# Sheet1.net
KiCad netlist of a schematic drawn in Altium Designer
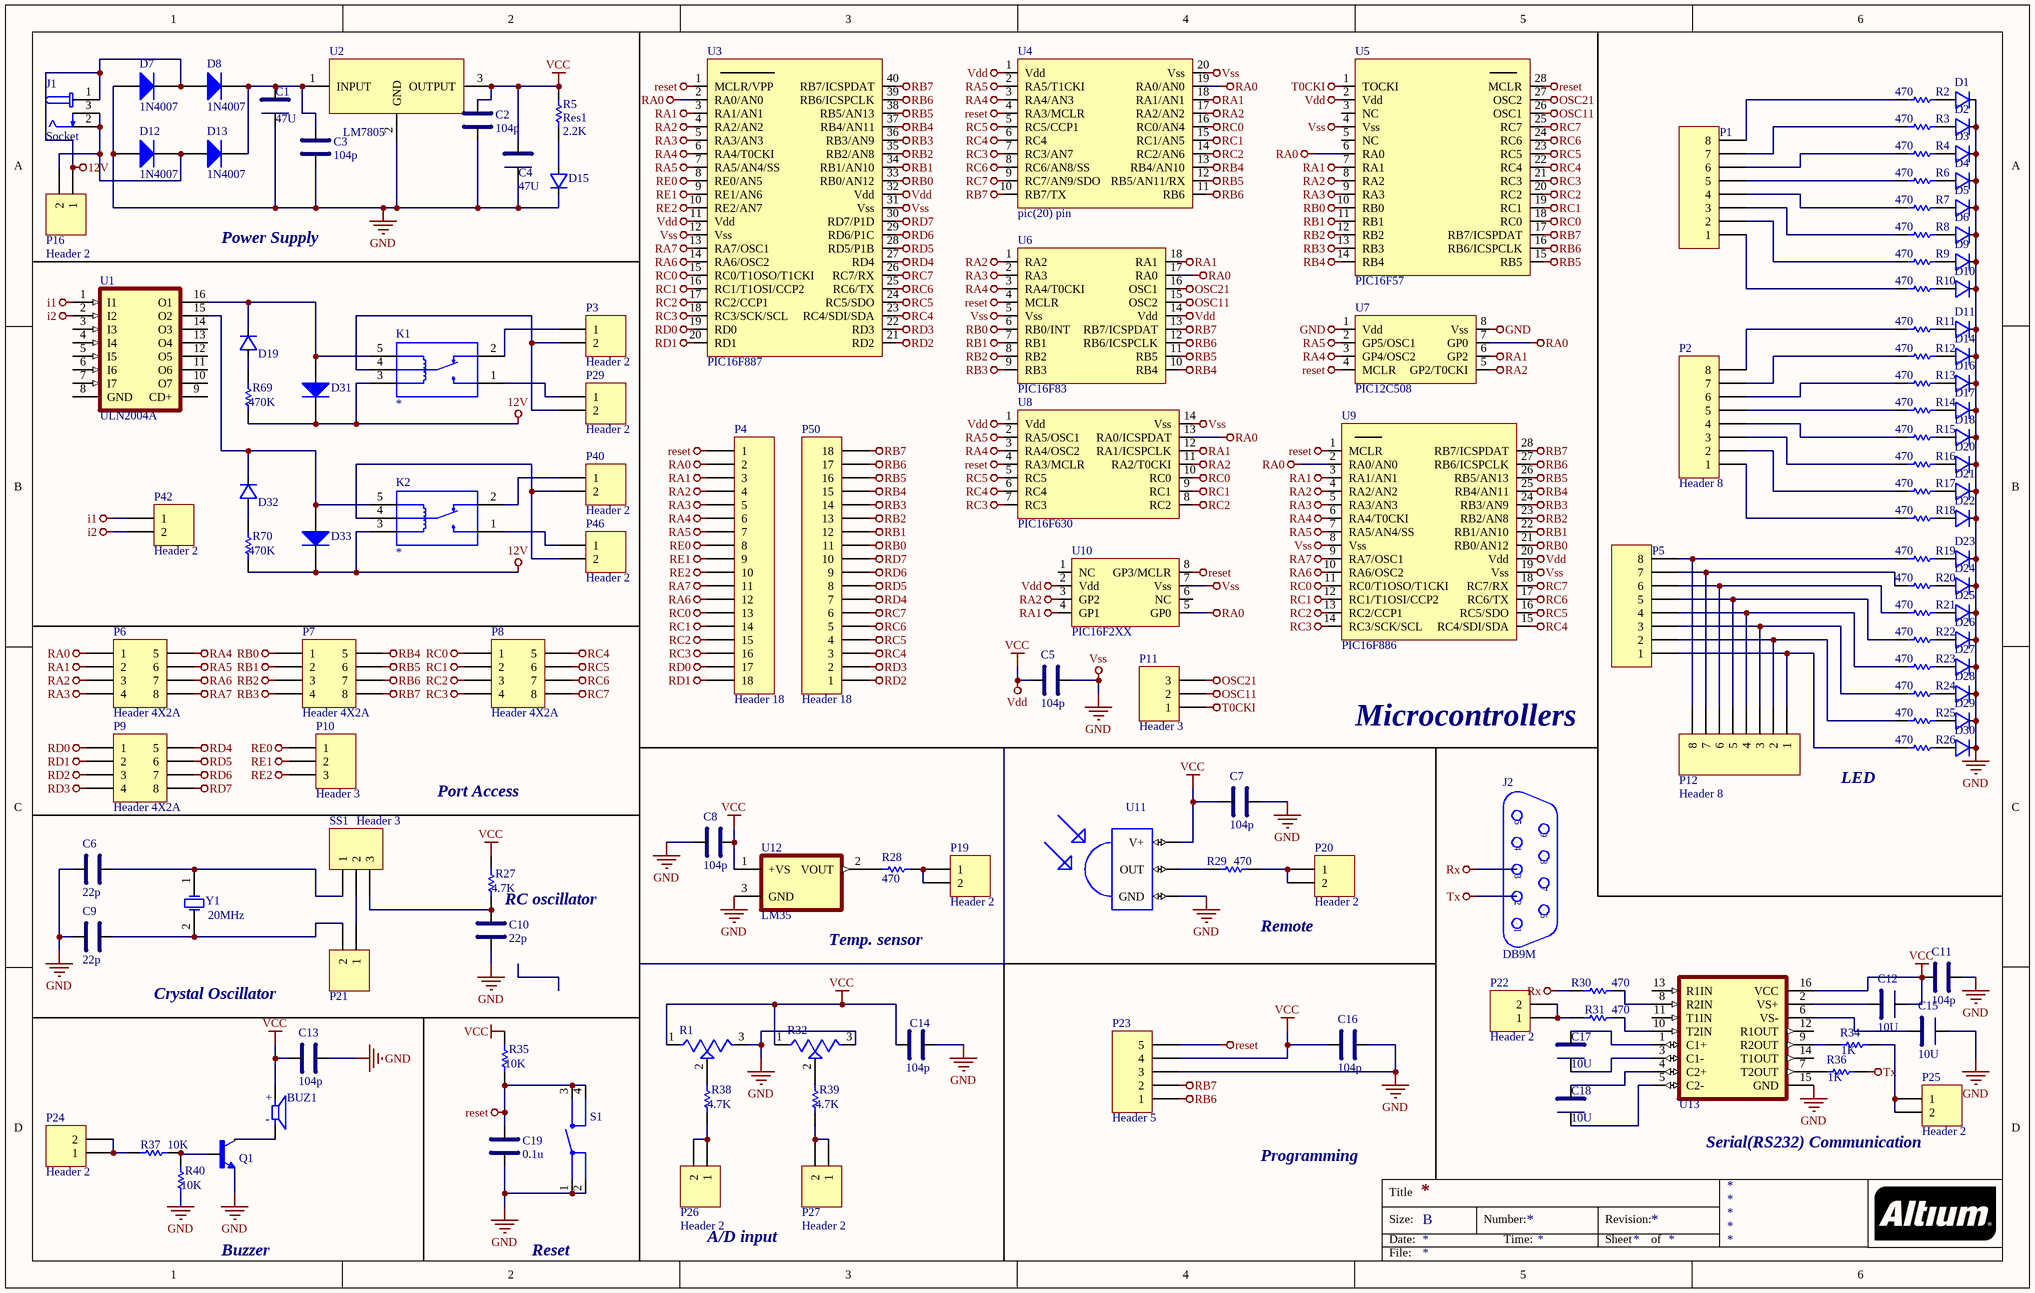
[diagram p0: Sheet1.SchDoc]

(export (version "E")
  (design (tool "Eeschema 10.0.6"))
  (components
    (comp (ref "BUZ1")
      (value "CEM-1203(42)")
      (footprint "SnapEDApcb:CUI_CEM-1203(42)")
      (description "12 mm, 3.5 V, 85 dB, Through Hole, Magnetic Audio Transducer Buzzer")
      (fields (field (name "MF") "CUI Devices") (field (name "MP") "CEM-1203_42_"))
      (libsource (lib "SnapEDAsch") (part "CEM-1203(42)"))
    )
    (comp (ref "C1") (value "47U") (footprint "polarityCAP") (libsource (lib "polarityCAP") (part "CAP")))
    (comp (ref "C2")
      (value "104p")
      (footprint "cap")
      (fields (field (name "Comment") "cap"))
      (libsource (lib "CAP") (part "cap"))
    )
    (comp (ref "C3") (value "104p") (footprint "cap") (libsource (lib "CAP") (part "cap")))
    (comp (ref "C4") (value "47U") (footprint "polarityCAP") (libsource (lib "polarityCAP") (part "CAP")))
    (comp (ref "C5")
      (value "104p")
      (footprint "cap")
      (fields (field (name "Comment") "cap"))
      (libsource (lib "CAP") (part "cap"))
    )
    (comp (ref "C6")
      (value "22p")
      (footprint "cap")
      (fields (field (name "Comment") "cap"))
      (libsource (lib "CAP") (part "cap"))
    )
    (comp (ref "C7")
      (value "104p")
      (footprint "cap")
      (fields (field (name "Comment") "cap"))
      (libsource (lib "CAP") (part "cap"))
    )
    (comp (ref "C8")
      (value "104p")
      (footprint "cap")
      (fields (field (name "Comment") "cap"))
      (libsource (lib "CAP") (part "cap"))
    )
    (comp (ref "C9")
      (value "22p")
      (footprint "cap")
      (fields (field (name "Comment") "cap"))
      (libsource (lib "CAP") (part "cap"))
    )
    (comp (ref "C10")
      (value "22p")
      (footprint "cap")
      (fields (field (name "Comment") "cap"))
      (libsource (lib "CAP") (part "cap"))
    )
    (comp (ref "C11")
      (value "104p")
      (footprint "cap")
      (fields (field (name "Comment") "cap"))
      (libsource (lib "CAP") (part "cap"))
    )
    (comp (ref "C12")
      (value "10U")
      (footprint "polarityCAP")
      (fields (field (name "Comment") "P.CAP"))
      (libsource (lib "polarityCAP") (part "CAP"))
    )
    (comp (ref "C13")
      (value "104p")
      (footprint "cap")
      (fields (field (name "Comment") "cap"))
      (libsource (lib "CAP") (part "cap"))
    )
    (comp (ref "C14")
      (value "104p")
      (footprint "cap")
      (fields (field (name "Comment") "cap"))
      (libsource (lib "CAP") (part "cap"))
    )
    (comp (ref "C15")
      (value "10U")
      (footprint "polarityCAP")
      (fields (field (name "Comment") "P.CAP"))
      (libsource (lib "polarityCAP") (part "CAP"))
    )
    (comp (ref "C16")
      (value "104p")
      (footprint "cap")
      (fields (field (name "Comment") "cap"))
      (libsource (lib "CAP") (part "cap"))
    )
    (comp (ref "C17")
      (value "10U")
      (footprint "polarityCAP")
      (fields (field (name "Comment") "P.CAP"))
      (libsource (lib "polarityCAP") (part "CAP"))
    )
    (comp (ref "C18")
      (value "10U")
      (footprint "polarityCAP")
      (fields (field (name "Comment") "P.CAP"))
      (libsource (lib "polarityCAP") (part "CAP"))
    )
    (comp (ref "C19")
      (value "0.1u")
      (footprint "cap")
      (fields (field (name "Comment") "cap"))
      (libsource (lib "CAP") (part "cap"))
    )
    (comp (ref "D1") (value "LED") (footprint "led:PCBComponent_1") (libsource (lib "led") (part "LED")))
    (comp (ref "D2") (value "LED") (footprint "led:PCBComponent_1") (libsource (lib "led") (part "LED")))
    (comp (ref "D3") (value "LED") (footprint "led:PCBComponent_1") (libsource (lib "led") (part "LED")))
    (comp (ref "D4") (value "LED") (footprint "led:PCBComponent_1") (libsource (lib "led") (part "LED")))
    (comp (ref "D5") (value "LED") (footprint "led:PCBComponent_1") (libsource (lib "led") (part "LED")))
    (comp (ref "D6") (value "LED") (footprint "led:PCBComponent_1") (libsource (lib "led") (part "LED")))
    (comp (ref "D7")
      (value "1N4007")
      (footprint "DO-41")
      (description "1 Amp General Purpose Rectifier")
      (fields (field (name "PUBLISHER") "Altium Limited"))
      (libsource (lib "Miscellaneous Devices") (part "Diode 1N4007"))
    )
    (comp (ref "D8")
      (value "1N4007")
      (footprint "DO-41")
      (description "1 Amp General Purpose Rectifier")
      (fields (field (name "PUBLISHER") "Altium Limited"))
      (libsource (lib "Miscellaneous Devices") (part "Diode 1N4007"))
    )
    (comp (ref "D9") (value "LED") (footprint "led:PCBComponent_1") (libsource (lib "led") (part "LED")))
    (comp (ref "D10") (value "LED") (footprint "led:PCBComponent_1") (libsource (lib "led") (part "LED")))
    (comp (ref "D11") (value "LED") (footprint "led:PCBComponent_1") (libsource (lib "led") (part "LED")))
    (comp (ref "D12")
      (value "1N4007")
      (footprint "DO-41")
      (description "1 Amp General Purpose Rectifier")
      (fields (field (name "PUBLISHER") "Altium Limited"))
      (libsource (lib "Miscellaneous Devices") (part "Diode 1N4007"))
    )
    (comp (ref "D13")
      (value "1N4007")
      (footprint "DO-41")
      (description "1 Amp General Purpose Rectifier")
      (fields (field (name "PUBLISHER") "Altium Limited"))
      (libsource (lib "Miscellaneous Devices") (part "Diode 1N4007"))
    )
    (comp (ref "D14") (value "LED") (footprint "led:PCBComponent_1") (libsource (lib "led") (part "LED")))
    (comp (ref "D15") (value "LED") (footprint "led:PCBComponent_1") (libsource (lib "led") (part "LED")))
    (comp (ref "D16") (value "LED") (footprint "led:PCBComponent_1") (libsource (lib "led") (part "LED")))
    (comp (ref "D17") (value "LED") (footprint "led:PCBComponent_1") (libsource (lib "led") (part "LED")))
    (comp (ref "D18") (value "LED") (footprint "led:PCBComponent_1") (libsource (lib "led") (part "LED")))
    (comp (ref "D19") (value "LED") (footprint "led:PCBComponent_1") (libsource (lib "led") (part "LED")))
    (comp (ref "D20") (value "LED") (footprint "led:PCBComponent_1") (libsource (lib "led") (part "LED")))
    (comp (ref "D21") (value "LED") (footprint "led:PCBComponent_1") (libsource (lib "led") (part "LED")))
    (comp (ref "D22") (value "LED") (footprint "led:PCBComponent_1") (libsource (lib "led") (part "LED")))
    (comp (ref "D23") (value "LED") (footprint "led:PCBComponent_1") (libsource (lib "led") (part "LED")))
    (comp (ref "D24") (value "LED") (footprint "led:PCBComponent_1") (libsource (lib "led") (part "LED")))
    (comp (ref "D25") (value "LED") (footprint "led:PCBComponent_1") (libsource (lib "led") (part "LED")))
    (comp (ref "D26") (value "LED") (footprint "led:PCBComponent_1") (libsource (lib "led") (part "LED")))
    (comp (ref "D27") (value "LED") (footprint "led:PCBComponent_1") (libsource (lib "led") (part "LED")))
    (comp (ref "D28") (value "LED") (footprint "led:PCBComponent_1") (libsource (lib "led") (part "LED")))
    (comp (ref "D29") (value "LED") (footprint "led:PCBComponent_1") (libsource (lib "led") (part "LED")))
    (comp (ref "D30") (value "LED") (footprint "led:PCBComponent_1") (libsource (lib "led") (part "LED")))
    (comp (ref "D31")
      (value "Diode 1N4007")
      (footprint "DO-41")
      (description "1 Amp General Purpose Rectifier")
      (fields (field (name "PUBLISHER") "Altium Limited"))
      (libsource (lib "Miscellaneous Devices") (part "Diode 1N4007"))
    )
    (comp (ref "D32") (value "LED") (footprint "led:PCBComponent_1") (libsource (lib "led") (part "LED")))
    (comp (ref "D33")
      (value "Diode 1N4007")
      (footprint "DO-41")
      (description "1 Amp General Purpose Rectifier")
      (fields (field (name "PUBLISHER") "Altium Limited"))
      (libsource (lib "Miscellaneous Devices") (part "Diode 1N4007"))
    )
    (comp (ref "J1")
      (value "Socket")
      (footprint "GCT_DCJ235-05-A-XX-X_REVA:GCT_DCJ235-05-A-XX-X_REVA")
      (description "Dc Power Jack, 5a, 20vdc, Black")
      (fields (field (name "MF") "Global Connector Technology") (field (name "MP") "DCJ235-05-A-K1-A"))
      (libsource (lib "DCJ235-05-A-XX-X_REVA") (part "DCJ235-05-A-XX-X_REVA"))
    )
    (comp (ref "J2")
      (value "DB9M")
      (footprint "DB9M:D-09M")
      (description "Adapter Connector D-Sub, 9 Pin Male To D-Sub, 9 Pin Male Free Hanging _In-Line_")
      (fields (field (name "MF") "NorComp Inc."))
      (libsource (lib "SnapEDAsch") (part "DB9M"))
    )
    (comp (ref "K1")
      (value "1-1721150-0")
      (footprint "relay:RELAY_ORWH-SH-105D1F,000")
      (description "Electromechanical Relay 5VDC 15A SPDT __ 19.2mm 15.5mm 15mm__ THT General Purpose Relay")
      (fields
        (field (name "MP") "ORWH-SH-105D1F,000")
        (field (name "MF") "TE Connectivity")
        (field (name "COMMENT_1") "*")
      )
      (libsource (lib "SnapEDAsch") (part "ORWH-SH-105D1F,000"))
    )
    (comp (ref "K2")
      (value "1-1721150-0")
      (footprint "relay:RELAY_ORWH-SH-105D1F,000")
      (description "Electromechanical Relay 5VDC 15A SPDT __ 19.2mm 15.5mm 15mm__ THT General Purpose Relay")
      (fields
        (field (name "MP") "ORWH-SH-105D1F,000")
        (field (name "MF") "TE Connectivity")
        (field (name "COMMENT_1") "*")
      )
      (libsource (lib "SnapEDAsch") (part "ORWH-SH-105D1F,000"))
    )
    (comp (ref "P1")
      (value "Header 8")
      (footprint "HDR1X8")
      (description "Header, 8-Pin")
      (fields (field (name "PUBLISHER") "Altium Limited"))
      (libsource (lib "Miscellaneous Connectors") (part "Header 8"))
    )
    (comp (ref "P2")
      (value "Header 8")
      (footprint "HDR1X8")
      (description "Header, 8-Pin")
      (fields (field (name "PUBLISHER") "Altium Limited"))
      (libsource (lib "Miscellaneous Connectors") (part "Header 8"))
    )
    (comp (ref "P3")
      (value "Header 2")
      (footprint "HDR1X2")
      (description "Header, 2-Pin")
      (fields (field (name "PUBLISHER") "Altium Limited"))
      (libsource (lib "Miscellaneous Connectors") (part "Header 2"))
    )
    (comp (ref "P4")
      (value "Header 18")
      (footprint "HDR1X18")
      (description "Header, 18-Pin")
      (fields (field (name "PUBLISHER") "Altium Limited"))
      (libsource (lib "Miscellaneous Connectors") (part "Header 18"))
    )
    (comp (ref "P5")
      (value "Header 8")
      (footprint "HDR1X8")
      (description "Header, 8-Pin")
      (fields (field (name "PUBLISHER") "Altium Limited"))
      (libsource (lib "Miscellaneous Connectors") (part "Header 8"))
    )
    (comp (ref "P6")
      (value "Header 4X2A")
      (footprint "HDR2X4_CEN")
      (description "Header, 4-Pin, Dual row")
      (fields (field (name "PUBLISHER") "Altium Limited"))
      (libsource (lib "Miscellaneous Connectors") (part "Header 4X2A"))
    )
    (comp (ref "P7")
      (value "Header 4X2A")
      (footprint "HDR2X4_CEN")
      (description "Header, 4-Pin, Dual row")
      (fields (field (name "PUBLISHER") "Altium Limited"))
      (libsource (lib "Miscellaneous Connectors") (part "Header 4X2A"))
    )
    (comp (ref "P8")
      (value "Header 4X2A")
      (footprint "HDR2X4_CEN")
      (description "Header, 4-Pin, Dual row")
      (fields (field (name "PUBLISHER") "Altium Limited"))
      (libsource (lib "Miscellaneous Connectors") (part "Header 4X2A"))
    )
    (comp (ref "P9")
      (value "Header 4X2A")
      (footprint "HDR2X4_CEN")
      (description "Header, 4-Pin, Dual row")
      (fields (field (name "PUBLISHER") "Altium Limited"))
      (libsource (lib "Miscellaneous Connectors") (part "Header 4X2A"))
    )
    (comp (ref "P10")
      (value "Header 3")
      (footprint "HDR1X3")
      (description "Header, 3-Pin")
      (fields (field (name "PUBLISHER") "Altium Limited"))
      (libsource (lib "") (part "Header 3_1"))
    )
    (comp (ref "P11")
      (value "Header 3")
      (footprint "HDR1X3")
      (description "Header, 3-Pin")
      (fields (field (name "PUBLISHER") "Altium Limited"))
      (libsource (lib "Miscellaneous Connectors") (part "Header 3"))
    )
    (comp (ref "P12")
      (value "Header 8")
      (footprint "HDR1X8")
      (description "Header, 8-Pin")
      (fields (field (name "PUBLISHER") "Altium Limited"))
      (libsource (lib "") (part "Header 8_1"))
    )
    (comp (ref "P16")
      (value "Header 2")
      (footprint "HDR1X2")
      (description "Header, 2-Pin")
      (fields (field (name "PUBLISHER") "Altium Limited"))
      (libsource (lib "") (part "Header 2_1"))
    )
    (comp (ref "P19")
      (value "Header 2")
      (footprint "HDR1X2")
      (description "Header, 2-Pin")
      (fields (field (name "PUBLISHER") "Altium Limited"))
      (libsource (lib "Miscellaneous Connectors") (part "Header 2"))
    )
    (comp (ref "P20")
      (value "Header 2")
      (footprint "HDR1X2")
      (description "Header, 2-Pin")
      (fields (field (name "PUBLISHER") "Altium Limited"))
      (libsource (lib "Miscellaneous Connectors") (part "Header 2"))
    )
    (comp (ref "P21")
      (value "Header 2")
      (footprint "HDR1X2")
      (description "Header, 2-Pin")
      (fields (field (name "PUBLISHER") "Altium Limited"))
      (libsource (lib "") (part "Header 2_1"))
    )
    (comp (ref "P22")
      (value "Header 2")
      (footprint "HDR1X2")
      (description "Header, 2-Pin")
      (fields (field (name "PUBLISHER") "Altium Limited"))
      (libsource (lib "") (part "Header 2_2"))
    )
    (comp (ref "P23")
      (value "Header 5")
      (footprint "HDR1X5")
      (description "Header, 5-Pin")
      (fields (field (name "PUBLISHER") "Altium Limited"))
      (libsource (lib "Miscellaneous Connectors") (part "Header 5"))
    )
    (comp (ref "P24")
      (value "Header 2")
      (footprint "HDR1X2")
      (description "Header, 2-Pin")
      (fields (field (name "PUBLISHER") "Altium Limited"))
      (libsource (lib "") (part "Header 2_2"))
    )
    (comp (ref "P25")
      (value "Header 2")
      (footprint "HDR1X2")
      (description "Header, 2-Pin")
      (fields (field (name "PUBLISHER") "Altium Limited"))
      (libsource (lib "Miscellaneous Connectors") (part "Header 2"))
    )
    (comp (ref "P26")
      (value "Header 2")
      (footprint "HDR1X2")
      (description "Header, 2-Pin")
      (fields (field (name "PUBLISHER") "Altium Limited"))
      (libsource (lib "") (part "Header 2_1"))
    )
    (comp (ref "P27")
      (value "Header 2")
      (footprint "HDR1X2")
      (description "Header, 2-Pin")
      (fields (field (name "PUBLISHER") "Altium Limited"))
      (libsource (lib "") (part "Header 2_1"))
    )
    (comp (ref "P29")
      (value "Header 2")
      (footprint "HDR1X2")
      (description "Header, 2-Pin")
      (fields (field (name "PUBLISHER") "Altium Limited"))
      (libsource (lib "Miscellaneous Connectors") (part "Header 2"))
    )
    (comp (ref "P40")
      (value "Header 2")
      (footprint "HDR1X2")
      (description "Header, 2-Pin")
      (fields (field (name "PUBLISHER") "Altium Limited"))
      (libsource (lib "Miscellaneous Connectors") (part "Header 2"))
    )
    (comp (ref "P42")
      (value "Header 2")
      (footprint "HDR1X2")
      (description "Header, 2-Pin")
      (fields (field (name "PUBLISHER") "Altium Limited"))
      (libsource (lib "Miscellaneous Connectors") (part "Header 2"))
    )
    (comp (ref "P46")
      (value "Header 2")
      (footprint "HDR1X2")
      (description "Header, 2-Pin")
      (fields (field (name "PUBLISHER") "Altium Limited"))
      (libsource (lib "Miscellaneous Connectors") (part "Header 2"))
    )
    (comp (ref "P50")
      (value "Header 18")
      (footprint "HDR1X18")
      (description "Header, 18-Pin")
      (fields (field (name "PUBLISHER") "Altium Limited"))
      (libsource (lib "") (part "Header 18_1"))
    )
    (comp (ref "Q1")
      (value "2N5172")
      (footprint "TRANSISTOR_TO-92:TRANSISTOR_TO-92")
      (description "Bipolar (BJT) Transistor NPN 25V 500mA 625mW Through Hole TO-92-3")
      (fields (field (name "MF") "ON Semiconductor"))
      (libsource (lib "2N5172") (part "2N5172"))
    )
    (comp (ref "R1")
      (value "3296W-1-103ALF")
      (footprint "TRIM_3296W-1-103ALF:TRIM_3296W-1-103ALF")
      (description "10 kOhms 0.5W, 1 / 2W PC Pins qua lá»— Trimmer Potentiometer Cermet 25 Turn Top Äiá»u chá»‰nh")
      (fields (field (name "MF") "Bourns"))
      (libsource (lib "3296W-1-103ALF") (part "3296W-1-103ALF"))
    )
    (comp (ref "R2")
      (value "470")
      (footprint "AXIAL-0.3")
      (description "Resistor")
      (fields (field (name "Comment") "Res1") (field (name "PUBLISHER") "Altium Limited"))
      (libsource (lib "Miscellaneous Devices") (part "Res1"))
    )
    (comp (ref "R3")
      (value "470")
      (footprint "AXIAL-0.3")
      (description "Resistor")
      (fields (field (name "Comment") "Res1") (field (name "PUBLISHER") "Altium Limited"))
      (libsource (lib "Miscellaneous Devices") (part "Res1"))
    )
    (comp (ref "R4")
      (value "470")
      (footprint "AXIAL-0.3")
      (description "Resistor")
      (fields (field (name "Comment") "Res1") (field (name "PUBLISHER") "Altium Limited"))
      (libsource (lib "Miscellaneous Devices") (part "Res1"))
    )
    (comp (ref "R5")
      (value "Res1")
      (footprint "AXIAL-0.3")
      (description "Resistor")
      (fields (field (name "ALTIUM_VALUE") "2.2K") (field (name "PUBLISHER") "Altium Limited"))
      (libsource (lib "Miscellaneous Devices") (part "Res1"))
    )
    (comp (ref "R6")
      (value "470")
      (footprint "AXIAL-0.3")
      (description "Resistor")
      (fields (field (name "Comment") "Res1") (field (name "PUBLISHER") "Altium Limited"))
      (libsource (lib "Miscellaneous Devices") (part "Res1"))
    )
    (comp (ref "R7")
      (value "470")
      (footprint "AXIAL-0.3")
      (description "Resistor")
      (fields (field (name "Comment") "Res1") (field (name "PUBLISHER") "Altium Limited"))
      (libsource (lib "Miscellaneous Devices") (part "Res1"))
    )
    (comp (ref "R8")
      (value "470")
      (footprint "AXIAL-0.3")
      (description "Resistor")
      (fields (field (name "Comment") "Res1") (field (name "PUBLISHER") "Altium Limited"))
      (libsource (lib "Miscellaneous Devices") (part "Res1"))
    )
    (comp (ref "R9")
      (value "470")
      (footprint "AXIAL-0.3")
      (description "Resistor")
      (fields (field (name "Comment") "Res1") (field (name "PUBLISHER") "Altium Limited"))
      (libsource (lib "Miscellaneous Devices") (part "Res1"))
    )
    (comp (ref "R10")
      (value "470")
      (footprint "AXIAL-0.3")
      (description "Resistor")
      (fields (field (name "Comment") "Res1") (field (name "PUBLISHER") "Altium Limited"))
      (libsource (lib "Miscellaneous Devices") (part "Res1"))
    )
    (comp (ref "R11")
      (value "470")
      (footprint "AXIAL-0.3")
      (description "Resistor")
      (fields (field (name "Comment") "Res1") (field (name "PUBLISHER") "Altium Limited"))
      (libsource (lib "Miscellaneous Devices") (part "Res1"))
    )
    (comp (ref "R12")
      (value "470")
      (footprint "AXIAL-0.3")
      (description "Resistor")
      (fields (field (name "Comment") "Res1") (field (name "PUBLISHER") "Altium Limited"))
      (libsource (lib "Miscellaneous Devices") (part "Res1"))
    )
    (comp (ref "R13")
      (value "470")
      (footprint "AXIAL-0.3")
      (description "Resistor")
      (fields (field (name "Comment") "Res1") (field (name "PUBLISHER") "Altium Limited"))
      (libsource (lib "Miscellaneous Devices") (part "Res1"))
    )
    (comp (ref "R14")
      (value "470")
      (footprint "AXIAL-0.3")
      (description "Resistor")
      (fields (field (name "Comment") "Res1") (field (name "PUBLISHER") "Altium Limited"))
      (libsource (lib "Miscellaneous Devices") (part "Res1"))
    )
    (comp (ref "R15")
      (value "470")
      (footprint "AXIAL-0.3")
      (description "Resistor")
      (fields (field (name "Comment") "Res1") (field (name "PUBLISHER") "Altium Limited"))
      (libsource (lib "Miscellaneous Devices") (part "Res1"))
    )
    (comp (ref "R16")
      (value "470")
      (footprint "AXIAL-0.3")
      (description "Resistor")
      (fields (field (name "Comment") "Res1") (field (name "PUBLISHER") "Altium Limited"))
      (libsource (lib "Miscellaneous Devices") (part "Res1"))
    )
    (comp (ref "R17")
      (value "470")
      (footprint "AXIAL-0.3")
      (description "Resistor")
      (fields (field (name "Comment") "Res1") (field (name "PUBLISHER") "Altium Limited"))
      (libsource (lib "Miscellaneous Devices") (part "Res1"))
    )
    (comp (ref "R18")
      (value "470")
      (footprint "AXIAL-0.3")
      (description "Resistor")
      (fields (field (name "Comment") "Res1") (field (name "PUBLISHER") "Altium Limited"))
      (libsource (lib "Miscellaneous Devices") (part "Res1"))
    )
    (comp (ref "R19")
      (value "470")
      (footprint "AXIAL-0.3")
      (description "Resistor")
      (fields (field (name "Comment") "Res1") (field (name "PUBLISHER") "Altium Limited"))
      (libsource (lib "Miscellaneous Devices") (part "Res1"))
    )
    (comp (ref "R20")
      (value "470")
      (footprint "AXIAL-0.3")
      (description "Resistor")
      (fields (field (name "Comment") "Res1") (field (name "PUBLISHER") "Altium Limited"))
      (libsource (lib "Miscellaneous Devices") (part "Res1"))
    )
    (comp (ref "R21")
      (value "470")
      (footprint "AXIAL-0.3")
      (description "Resistor")
      (fields (field (name "Comment") "Res1") (field (name "PUBLISHER") "Altium Limited"))
      (libsource (lib "Miscellaneous Devices") (part "Res1"))
    )
    (comp (ref "R22")
      (value "470")
      (footprint "AXIAL-0.3")
      (description "Resistor")
      (fields (field (name "Comment") "Res1") (field (name "PUBLISHER") "Altium Limited"))
      (libsource (lib "Miscellaneous Devices") (part "Res1"))
    )
    (comp (ref "R23")
      (value "470")
      (footprint "AXIAL-0.3")
      (description "Resistor")
      (fields (field (name "Comment") "Res1") (field (name "PUBLISHER") "Altium Limited"))
      (libsource (lib "Miscellaneous Devices") (part "Res1"))
    )
    (comp (ref "R24")
      (value "470")
      (footprint "AXIAL-0.3")
      (description "Resistor")
      (fields (field (name "Comment") "Res1") (field (name "PUBLISHER") "Altium Limited"))
      (libsource (lib "Miscellaneous Devices") (part "Res1"))
    )
    (comp (ref "R25")
      (value "470")
      (footprint "AXIAL-0.3")
      (description "Resistor")
      (fields (field (name "Comment") "Res1") (field (name "PUBLISHER") "Altium Limited"))
      (libsource (lib "Miscellaneous Devices") (part "Res1"))
    )
    (comp (ref "R26")
      (value "470")
      (footprint "AXIAL-0.3")
      (description "Resistor")
      (fields (field (name "Comment") "Res1") (field (name "PUBLISHER") "Altium Limited"))
      (libsource (lib "Miscellaneous Devices") (part "Res1"))
    )
    (comp (ref "R27")
      (value "4.7K")
      (footprint "AXIAL-0.3")
      (description "Resistor")
      (fields (field (name "Comment") "Res1") (field (name "PUBLISHER") "Altium Limited"))
      (libsource (lib "Miscellaneous Devices") (part "Res1"))
    )
    (comp (ref "R28")
      (value "470")
      (footprint "AXIAL-0.3")
      (description "Resistor")
      (fields (field (name "Comment") "Res1") (field (name "PUBLISHER") "Altium Limited"))
      (libsource (lib "Miscellaneous Devices") (part "Res1"))
    )
    (comp (ref "R29")
      (value "470")
      (footprint "AXIAL-0.3")
      (description "Resistor")
      (fields (field (name "Comment") "Res1") (field (name "PUBLISHER") "Altium Limited"))
      (libsource (lib "Miscellaneous Devices") (part "Res1"))
    )
    (comp (ref "R30")
      (value "470")
      (footprint "AXIAL-0.3")
      (description "Resistor")
      (fields (field (name "Comment") "Res1") (field (name "PUBLISHER") "Altium Limited"))
      (libsource (lib "Miscellaneous Devices") (part "Res1"))
    )
    (comp (ref "R31")
      (value "470")
      (footprint "AXIAL-0.3")
      (description "Resistor")
      (fields (field (name "Comment") "Res1") (field (name "PUBLISHER") "Altium Limited"))
      (libsource (lib "Miscellaneous Devices") (part "Res1"))
    )
    (comp (ref "R32")
      (value "3296W-1-103ALF")
      (footprint "TRIM_3296W-1-103ALF:TRIM_3296W-1-103ALF")
      (description "10 kOhms 0.5W, 1 / 2W PC Pins qua lá»— Trimmer Potentiometer Cermet 25 Turn Top Äiá»u chá»‰nh")
      (fields (field (name "MF") "Bourns"))
      (libsource (lib "3296W-1-103ALF") (part "3296W-1-103ALF"))
    )
    (comp (ref "R34")
      (value "1K")
      (footprint "AXIAL-0.3")
      (description "Resistor")
      (fields (field (name "Comment") "Res1") (field (name "PUBLISHER") "Altium Limited"))
      (libsource (lib "Miscellaneous Devices") (part "Res1"))
    )
    (comp (ref "R35")
      (value "10K")
      (footprint "AXIAL-0.3")
      (description "Resistor")
      (fields (field (name "Comment") "Res1") (field (name "PUBLISHER") "Altium Limited"))
      (libsource (lib "Miscellaneous Devices") (part "Res1"))
    )
    (comp (ref "R36")
      (value "1K")
      (footprint "AXIAL-0.3")
      (description "Resistor")
      (fields (field (name "Comment") "Res1") (field (name "PUBLISHER") "Altium Limited"))
      (libsource (lib "Miscellaneous Devices") (part "Res1"))
    )
    (comp (ref "R37")
      (value "10K")
      (footprint "AXIAL-0.3")
      (description "Resistor")
      (fields (field (name "Comment") "Res1") (field (name "PUBLISHER") "Altium Limited"))
      (libsource (lib "Miscellaneous Devices") (part "Res1"))
    )
    (comp (ref "R38")
      (value "4.7K")
      (footprint "AXIAL-0.3")
      (description "Resistor")
      (fields (field (name "Comment") "Res1") (field (name "PUBLISHER") "Altium Limited"))
      (libsource (lib "Miscellaneous Devices") (part "Res1"))
    )
    (comp (ref "R39")
      (value "4.7K")
      (footprint "AXIAL-0.3")
      (description "Resistor")
      (fields (field (name "Comment") "Res1") (field (name "PUBLISHER") "Altium Limited"))
      (libsource (lib "Miscellaneous Devices") (part "Res1"))
    )
    (comp (ref "R40")
      (value "10K")
      (footprint "AXIAL-0.3")
      (description "Resistor")
      (fields (field (name "Comment") "Res1") (field (name "PUBLISHER") "Altium Limited"))
      (libsource (lib "Miscellaneous Devices") (part "Res1"))
    )
    (comp (ref "R69")
      (value "470K")
      (footprint "AXIAL-0.3")
      (description "Resistor")
      (fields (field (name "Comment") "Res1") (field (name "PUBLISHER") "Altium Limited"))
      (libsource (lib "Miscellaneous Devices") (part "Res1"))
    )
    (comp (ref "R70")
      (value "470K")
      (footprint "AXIAL-0.3")
      (description "Resistor")
      (fields (field (name "Comment") "Res1") (field (name "PUBLISHER") "Altium Limited"))
      (libsource (lib "Miscellaneous Devices") (part "Res1"))
    )
    (comp (ref "S1")
      (value "SKHHANA010")
      (footprint "SnapEDApcb:SW_SKHHANA010")
      (description "Switch Tactile N.O. SPST Round Button PC Pins 0.05A 12VDC 0.98N Thru-Hole Bulk")
      (fields (field (name "MF") "ALPS"))
      (libsource (lib "SnapEDAsch") (part "SKHHANA010"))
    )
    (comp (ref "SS1")
      (value "Header 3")
      (footprint "HDR1X3")
      (description "Header, 3-Pin")
      (fields (field (name "PUBLISHER") "Altium Limited"))
      (libsource (lib "") (part "Header 3_2"))
    )
    (comp (ref "U1")
      (value "ULN2004A")
      (footprint "ULN2004A:ULN2004A")
      (fields (field (name "MF") "STMicroelectronics"))
      (libsource (lib "SnapEDAsch") (part "ULN2004A"))
    )
    (comp (ref "U2")
      (value "LM7805")
      (footprint "LM7805:LM7805")
      (libsource (lib "LM7805") (part "Component_1"))
    )
    (comp (ref "U3")
      (value "PIC16F887")
      (footprint "PIC(40pin)")
      (libsource (lib "PIC(40)pin") (part "PIC(40)pin"))
    )
    (comp (ref "U4")
      (value "pic(20) pin")
      (footprint "PIC(20)piN")
      (libsource (lib "PIC(20)pin") (part "pic(20) pin"))
    )
    (comp (ref "U5")
      (value "PIC16F57")
      (footprint "PIC(28) pin")
      (libsource (lib "PIC16F57") (part "PIC16F57"))
    )
    (comp (ref "U6")
      (value "PIC16F83")
      (footprint "pic16F54")
      (libsource (lib "PIC(18)pin") (part "pic(18) pin"))
    )
    (comp (ref "U7")
      (value "PIC12C508")
      (footprint "PIC(8)pinbasic:PIC10F220")
      (libsource (lib "PIC(8)pinall") (part "PIC(8)pin"))
    )
    (comp (ref "U8")
      (value "PIC16F630")
      (footprint "PIC16f630")
      (libsource (lib "PIC(14)pin") (part "PIC(14) pin"))
    )
    (comp (ref "U9")
      (value "PIC16F886")
      (footprint "PIC(28) pin")
      (libsource (lib "PIC(28)pin") (part "PIC(28)pin"))
    )
    (comp (ref "U10")
      (value "PIC16F2XX")
      (footprint "PIC(8)pinbasic:PIC10F220")
      (libsource (lib "PIC(8)pinbasic") (part "PIC16F2XX"))
    )
    (comp (ref "U11")
      (value "1838V")
      (footprint "1838V:TSOP18XX")
      (description "Remote Receiver Sensor, 38.0kHz 45m Through Hole")
      (fields (field (name "MP") "TSOP4838") (field (name "MF") "Vishay"))
      (libsource (lib "SnapEDAsch") (part "1838V"))
    )
    (comp (ref "U12")
      (value "LM35")
      (footprint "lm35:TO127P254X495-3P")
      (description "&plusmn;0.5&deg;C 4V-30V, Temperature sensor with analog output 3-TO-92")
      (fields (field (name "MF") "Texas Instruments") (field (name "MP") "LM35CZ/LFT1"))
      (libsource (lib "LM35") (part "LM35"))
    )
    (comp (ref "U13")
      (value "MAX232")
      (footprint "DIP794W45P254L1969H508Q16:DIP794W45P254L1969H508Q16")
      (description "Dual EIA-232 Driver/Receiver")
      (fields (field (name "MP") "MAX232N") (field (name "MF") "Texas Instruments"))
      (libsource (lib "MAX232N") (part "MAX232N"))
    )
    (comp (ref "Y1")
      (value "20MHz")
      (footprint "R38")
      (description "Crystal Oscillator")
      (fields (field (name "Comment") "XTAL") (field (name "PUBLISHER") "Altium Limited"))
      (libsource (lib "Miscellaneous Devices") (part "XTAL"))
    )
  )
  (nets
    (net (code "1") (name "12V") (class "Default")
      (node (ref "D31") (pin "2") (pinfunction "K_2") (pintype "passive"))
      (node (ref "D33") (pin "2") (pinfunction "K_2") (pintype "passive"))
      (node (ref "D7") (pin "2") (pinfunction "K_2") (pintype "passive"))
      (node (ref "D8") (pin "1") (pinfunction "A_1") (pintype "passive"))
      (node (ref "J1") (pin "1") (pinfunction "1_1") (pintype "passive"))
      (node (ref "K1") (pin "3") (pinfunction "C1_3") (pintype "passive"))
      (node (ref "K2") (pin "3") (pinfunction "C1_3") (pintype "passive"))
      (node (ref "P16") (pin "1") (pinfunction "1_1") (pintype "passive"))
      (node (ref "R69") (pin "1") (pinfunction "1_1") (pintype "passive"))
      (node (ref "R70") (pin "1") (pinfunction "1_1") (pintype "passive"))
    )
    (net (code "2") (name "GND") (class "Default")
      (node (ref "C1") (pin "2") (pinfunction "2_2") (pintype "passive"))
      (node (ref "C10") (pin "1") (pinfunction "1_1") (pintype "passive"))
      (node (ref "C11") (pin "1") (pinfunction "1_1") (pintype "passive"))
      (node (ref "C13") (pin "1") (pinfunction "1_1") (pintype "passive"))
      (node (ref "C14") (pin "1") (pinfunction "1_1") (pintype "passive"))
      (node (ref "C15") (pin "2") (pinfunction "2_2") (pintype "passive"))
      (node (ref "C16") (pin "1") (pinfunction "1_1") (pintype "passive"))
      (node (ref "C19") (pin "1") (pinfunction "1_1") (pintype "passive"))
      (node (ref "C2") (pin "1") (pinfunction "1_1") (pintype "passive"))
      (node (ref "C3") (pin "1") (pinfunction "1_1") (pintype "passive"))
      (node (ref "C4") (pin "2") (pinfunction "2_2") (pintype "passive"))
      (node (ref "C5") (pin "1") (pinfunction "1_1") (pintype "passive"))
      (node (ref "C6") (pin "2") (pinfunction "2_2") (pintype "passive"))
      (node (ref "C7") (pin "1") (pinfunction "1_1") (pintype "passive"))
      (node (ref "C8") (pin "2") (pinfunction "2_2") (pintype "passive"))
      (node (ref "C9") (pin "2") (pinfunction "2_2") (pintype "passive"))
      (node (ref "D1") (pin "2") (pintype "passive"))
      (node (ref "D10") (pin "2") (pintype "passive"))
      (node (ref "D11") (pin "2") (pintype "passive"))
      (node (ref "D12") (pin "1") (pinfunction "A_1") (pintype "passive"))
      (node (ref "D14") (pin "2") (pintype "passive"))
      (node (ref "D15") (pin "2") (pintype "passive"))
      (node (ref "D16") (pin "2") (pintype "passive"))
      (node (ref "D17") (pin "2") (pintype "passive"))
      (node (ref "D18") (pin "2") (pintype "passive"))
      (node (ref "D2") (pin "2") (pintype "passive"))
      (node (ref "D20") (pin "2") (pintype "passive"))
      (node (ref "D21") (pin "2") (pintype "passive"))
      (node (ref "D22") (pin "2") (pintype "passive"))
      (node (ref "D23") (pin "2") (pintype "passive"))
      (node (ref "D24") (pin "2") (pintype "passive"))
      (node (ref "D25") (pin "2") (pintype "passive"))
      (node (ref "D26") (pin "2") (pintype "passive"))
      (node (ref "D27") (pin "2") (pintype "passive"))
      (node (ref "D28") (pin "2") (pintype "passive"))
      (node (ref "D29") (pin "2") (pintype "passive"))
      (node (ref "D3") (pin "2") (pintype "passive"))
      (node (ref "D30") (pin "2") (pintype "passive"))
      (node (ref "D4") (pin "2") (pintype "passive"))
      (node (ref "D5") (pin "2") (pintype "passive"))
      (node (ref "D6") (pin "2") (pintype "passive"))
      (node (ref "D7") (pin "1") (pinfunction "A_1") (pintype "passive"))
      (node (ref "D9") (pin "2") (pintype "passive"))
      (node (ref "P23") (pin "3") (pinfunction "3_3") (pintype "passive"))
      (node (ref "Q1") (pin "3") (pinfunction "E_3") (pintype "passive"))
      (node (ref "R1") (pin "3") (pinfunction "CW_3") (pintype "passive"))
      (node (ref "R32") (pin "3") (pinfunction "CW_3") (pintype "passive"))
      (node (ref "R40") (pin "1") (pinfunction "1_1") (pintype "passive"))
      (node (ref "S1") (pin "1") (pinfunction "1_1") (pintype "passive"))
      (node (ref "S1") (pin "2") (pinfunction "2_2") (pintype "passive"))
      (node (ref "U10") (pin "7") (pinfunction "Vss_7") (pintype "passive"))
      (node (ref "U11") (pin "GND") (pinfunction "GND_GND") (pintype "bidirectional"))
      (node (ref "U12") (pin "3") (pinfunction "GND_3") (pintype "passive"))
      (node (ref "U13") (pin "15") (pinfunction "GND_15") (pintype "power_in"))
      (node (ref "U2") (pin "2") (pinfunction "GND_2") (pintype "passive"))
      (node (ref "U3") (pin "12") (pinfunction "Vss_12") (pintype "passive"))
      (node (ref "U3") (pin "31") (pinfunction "Vss_31") (pintype "passive"))
      (node (ref "U4") (pin "20") (pinfunction "Vss_20") (pintype "passive"))
      (node (ref "U5") (pin "4") (pinfunction "Vss_4") (pintype "passive"))
      (node (ref "U6") (pin "5") (pinfunction "Vss_5") (pintype "passive"))
      (node (ref "U7") (pin "1") (pinfunction "Vdd_1") (pintype "passive"))
      (node (ref "U7") (pin "8") (pinfunction "Vss_8") (pintype "passive"))
      (node (ref "U8") (pin "14") (pinfunction "Vss_14") (pintype "passive"))
      (node (ref "U9") (pin "19") (pinfunction "Vss_19") (pintype "passive"))
      (node (ref "U9") (pin "8") (pinfunction "Vss_8") (pintype "passive"))
    )
    (net (code "3") (name "Net-(C10-Pad2)") (class "Default")
      (node (ref "C10") (pin "2") (pinfunction "2_2") (pintype "passive"))
      (node (ref "R27") (pin "1") (pinfunction "1_1") (pintype "passive"))
      (node (ref "SS1") (pin "3") (pinfunction "3_3") (pintype "passive"))
    )
    (net (code "4") (name "Net-(D1-Pad1)") (class "Default")
      (node (ref "D1") (pin "1") (pinfunction "1_1") (pintype "passive"))
      (node (ref "R2") (pin "2") (pinfunction "2_2") (pintype "passive"))
    )
    (net (code "5") (name "Net-(D2-Pad1)") (class "Default")
      (node (ref "D2") (pin "1") (pinfunction "1_1") (pintype "passive"))
      (node (ref "R3") (pin "2") (pinfunction "2_2") (pintype "passive"))
    )
    (net (code "6") (name "Net-(D3-Pad1)") (class "Default")
      (node (ref "D3") (pin "1") (pinfunction "1_1") (pintype "passive"))
      (node (ref "R4") (pin "2") (pinfunction "2_2") (pintype "passive"))
    )
    (net (code "7") (name "Net-(D4-Pad1)") (class "Default")
      (node (ref "D4") (pin "1") (pinfunction "1_1") (pintype "passive"))
      (node (ref "R6") (pin "2") (pinfunction "2_2") (pintype "passive"))
    )
    (net (code "8") (name "Net-(D5-Pad1)") (class "Default")
      (node (ref "D5") (pin "1") (pinfunction "1_1") (pintype "passive"))
      (node (ref "R7") (pin "2") (pinfunction "2_2") (pintype "passive"))
    )
    (net (code "9") (name "Net-(D6-Pad1)") (class "Default")
      (node (ref "D6") (pin "1") (pinfunction "1_1") (pintype "passive"))
      (node (ref "R8") (pin "2") (pinfunction "2_2") (pintype "passive"))
    )
    (net (code "10") (name "Net-(D9-Pad1)") (class "Default")
      (node (ref "D9") (pin "1") (pinfunction "1_1") (pintype "passive"))
      (node (ref "R9") (pin "2") (pinfunction "2_2") (pintype "passive"))
    )
    (net (code "11") (name "Net-(D10-Pad1)") (class "Default")
      (node (ref "D10") (pin "1") (pinfunction "1_1") (pintype "passive"))
      (node (ref "R10") (pin "2") (pinfunction "2_2") (pintype "passive"))
    )
    (net (code "12") (name "Net-(D11-Pad1)") (class "Default")
      (node (ref "D11") (pin "1") (pinfunction "1_1") (pintype "passive"))
      (node (ref "R11") (pin "2") (pinfunction "2_2") (pintype "passive"))
    )
    (net (code "13") (name "Net-(D12-K)") (class "Default")
      (node (ref "D12") (pin "2") (pinfunction "K_2") (pintype "passive"))
      (node (ref "D13") (pin "1") (pinfunction "A_1") (pintype "passive"))
      (node (ref "J1") (pin "2") (pinfunction "2_2") (pintype "passive"))
      (node (ref "J1") (pin "3") (pinfunction "3_3") (pintype "passive"))
      (node (ref "P16") (pin "2") (pinfunction "2_2") (pintype "passive"))
    )
    (net (code "14") (name "Net-(D13-K)") (class "Default")
      (node (ref "C1") (pin "1") (pinfunction "1_1") (pintype "passive"))
      (node (ref "C3") (pin "2") (pinfunction "2_2") (pintype "passive"))
      (node (ref "D13") (pin "2") (pinfunction "K_2") (pintype "passive"))
      (node (ref "D8") (pin "2") (pinfunction "K_2") (pintype "passive"))
      (node (ref "U2") (pin "1") (pinfunction "INPUT_1") (pintype "passive"))
    )
    (net (code "15") (name "Net-(D14-Pad1)") (class "Default")
      (node (ref "D14") (pin "1") (pinfunction "1_1") (pintype "passive"))
      (node (ref "R12") (pin "2") (pinfunction "2_2") (pintype "passive"))
    )
    (net (code "16") (name "Net-(D15-Pad1)") (class "Default")
      (node (ref "D15") (pin "1") (pinfunction "1_1") (pintype "passive"))
      (node (ref "R5") (pin "1") (pinfunction "1_1") (pintype "passive"))
    )
    (net (code "17") (name "Net-(D16-Pad1)") (class "Default")
      (node (ref "D16") (pin "1") (pinfunction "1_1") (pintype "passive"))
      (node (ref "R13") (pin "2") (pinfunction "2_2") (pintype "passive"))
    )
    (net (code "18") (name "Net-(D17-Pad1)") (class "Default")
      (node (ref "D17") (pin "1") (pinfunction "1_1") (pintype "passive"))
      (node (ref "R14") (pin "2") (pinfunction "2_2") (pintype "passive"))
    )
    (net (code "19") (name "Net-(D18-Pad1)") (class "Default")
      (node (ref "D18") (pin "1") (pinfunction "1_1") (pintype "passive"))
      (node (ref "R15") (pin "2") (pinfunction "2_2") (pintype "passive"))
    )
    (net (code "20") (name "Net-(D19-Pad1)") (class "Default")
      (node (ref "D19") (pin "1") (pinfunction "1_1") (pintype "passive"))
      (node (ref "R69") (pin "2") (pinfunction "2_2") (pintype "passive"))
    )
    (net (code "21") (name "Net-(D20-Pad1)") (class "Default")
      (node (ref "D20") (pin "1") (pinfunction "1_1") (pintype "passive"))
      (node (ref "R16") (pin "2") (pinfunction "2_2") (pintype "passive"))
    )
    (net (code "22") (name "Net-(D21-Pad1)") (class "Default")
      (node (ref "D21") (pin "1") (pinfunction "1_1") (pintype "passive"))
      (node (ref "R17") (pin "2") (pinfunction "2_2") (pintype "passive"))
    )
    (net (code "23") (name "Net-(D22-Pad1)") (class "Default")
      (node (ref "D22") (pin "1") (pinfunction "1_1") (pintype "passive"))
      (node (ref "R18") (pin "2") (pinfunction "2_2") (pintype "passive"))
    )
    (net (code "24") (name "Net-(D23-Pad1)") (class "Default")
      (node (ref "D23") (pin "1") (pinfunction "1_1") (pintype "passive"))
      (node (ref "R19") (pin "2") (pinfunction "2_2") (pintype "passive"))
    )
    (net (code "25") (name "Net-(D24-Pad1)") (class "Default")
      (node (ref "D24") (pin "1") (pinfunction "1_1") (pintype "passive"))
      (node (ref "R20") (pin "2") (pinfunction "2_2") (pintype "passive"))
    )
    (net (code "26") (name "Net-(D25-Pad1)") (class "Default")
      (node (ref "D25") (pin "1") (pinfunction "1_1") (pintype "passive"))
      (node (ref "R21") (pin "2") (pinfunction "2_2") (pintype "passive"))
    )
    (net (code "27") (name "Net-(D26-Pad1)") (class "Default")
      (node (ref "D26") (pin "1") (pinfunction "1_1") (pintype "passive"))
      (node (ref "R22") (pin "2") (pinfunction "2_2") (pintype "passive"))
    )
    (net (code "28") (name "Net-(D27-Pad1)") (class "Default")
      (node (ref "D27") (pin "1") (pinfunction "1_1") (pintype "passive"))
      (node (ref "R23") (pin "2") (pinfunction "2_2") (pintype "passive"))
    )
    (net (code "29") (name "Net-(D28-Pad1)") (class "Default")
      (node (ref "D28") (pin "1") (pinfunction "1_1") (pintype "passive"))
      (node (ref "R24") (pin "2") (pinfunction "2_2") (pintype "passive"))
    )
    (net (code "30") (name "Net-(D29-Pad1)") (class "Default")
      (node (ref "D29") (pin "1") (pinfunction "1_1") (pintype "passive"))
      (node (ref "R25") (pin "2") (pinfunction "2_2") (pintype "passive"))
    )
    (net (code "31") (name "Net-(D30-Pad1)") (class "Default")
      (node (ref "D30") (pin "1") (pinfunction "1_1") (pintype "passive"))
      (node (ref "R26") (pin "2") (pinfunction "2_2") (pintype "passive"))
    )
    (net (code "32") (name "Net-(D31-A)") (class "Default")
      (node (ref "D19") (pin "2") (pintype "passive"))
      (node (ref "D31") (pin "1") (pinfunction "A_1") (pintype "passive"))
      (node (ref "K1") (pin "5") (pinfunction "C2_5") (pintype "passive"))
      (node (ref "U1") (pin "16") (pinfunction "O1_16") (pintype "open_collector"))
    )
    (net (code "33") (name "Net-(D32-Pad1)") (class "Default")
      (node (ref "D32") (pin "1") (pinfunction "1_1") (pintype "passive"))
      (node (ref "R70") (pin "2") (pinfunction "2_2") (pintype "passive"))
    )
    (net (code "34") (name "Net-(D33-A)") (class "Default")
      (node (ref "D32") (pin "2") (pintype "passive"))
      (node (ref "D33") (pin "1") (pinfunction "A_1") (pintype "passive"))
      (node (ref "K2") (pin "5") (pinfunction "C2_5") (pintype "passive"))
      (node (ref "U1") (pin "15") (pinfunction "O2_15") (pintype "open_collector"))
    )
    (net (code "35") (name "Net-(K1-C)") (class "Default")
      (node (ref "K1") (pin "4") (pinfunction "C_4") (pintype "passive"))
      (node (ref "P29") (pin "2") (pinfunction "2_2") (pintype "passive"))
      (node (ref "P3") (pin "2") (pinfunction "2_2") (pintype "passive"))
    )
    (net (code "36") (name "Net-(K1-NC)") (class "Default")
      (node (ref "K1") (pin "2") (pinfunction "NC_2") (pintype "passive"))
      (node (ref "P3") (pin "1") (pinfunction "1_1") (pintype "passive"))
    )
    (net (code "37") (name "Net-(K1-NO)") (class "Default")
      (node (ref "K1") (pin "1") (pinfunction "NO_1") (pintype "passive"))
      (node (ref "P29") (pin "1") (pinfunction "1_1") (pintype "passive"))
    )
    (net (code "38") (name "Net-(K2-C)") (class "Default")
      (node (ref "K2") (pin "4") (pinfunction "C_4") (pintype "passive"))
      (node (ref "P40") (pin "2") (pinfunction "2_2") (pintype "passive"))
      (node (ref "P46") (pin "2") (pinfunction "2_2") (pintype "passive"))
    )
    (net (code "39") (name "Net-(K2-NC)") (class "Default")
      (node (ref "K2") (pin "2") (pinfunction "NC_2") (pintype "passive"))
      (node (ref "P40") (pin "1") (pinfunction "1_1") (pintype "passive"))
    )
    (net (code "40") (name "Net-(K2-NO)") (class "Default")
      (node (ref "K2") (pin "1") (pinfunction "NO_1") (pintype "passive"))
      (node (ref "P46") (pin "1") (pinfunction "1_1") (pintype "passive"))
    )
    (net (code "41") (name "Net-(P1-Pad1)") (class "Default")
      (node (ref "P1") (pin "1") (pinfunction "1_1") (pintype "passive"))
      (node (ref "R10") (pin "1") (pinfunction "1_1") (pintype "passive"))
    )
    (net (code "42") (name "Net-(P1-Pad2)") (class "Default")
      (node (ref "P1") (pin "2") (pinfunction "2_2") (pintype "passive"))
      (node (ref "R9") (pin "1") (pinfunction "1_1") (pintype "passive"))
    )
    (net (code "43") (name "Net-(P1-Pad3)") (class "Default")
      (node (ref "P1") (pin "3") (pinfunction "3_3") (pintype "passive"))
      (node (ref "R8") (pin "1") (pinfunction "1_1") (pintype "passive"))
    )
    (net (code "44") (name "Net-(P1-Pad4)") (class "Default")
      (node (ref "P1") (pin "4") (pinfunction "4_4") (pintype "passive"))
      (node (ref "R7") (pin "1") (pinfunction "1_1") (pintype "passive"))
    )
    (net (code "45") (name "Net-(P1-Pad5)") (class "Default")
      (node (ref "P1") (pin "5") (pinfunction "5_5") (pintype "passive"))
      (node (ref "R6") (pin "1") (pinfunction "1_1") (pintype "passive"))
    )
    (net (code "46") (name "Net-(P1-Pad6)") (class "Default")
      (node (ref "P1") (pin "6") (pinfunction "6_6") (pintype "passive"))
      (node (ref "R4") (pin "1") (pinfunction "1_1") (pintype "passive"))
    )
    (net (code "47") (name "Net-(P1-Pad7)") (class "Default")
      (node (ref "P1") (pin "7") (pinfunction "7_7") (pintype "passive"))
      (node (ref "R3") (pin "1") (pinfunction "1_1") (pintype "passive"))
    )
    (net (code "48") (name "Net-(P1-Pad8)") (class "Default")
      (node (ref "P1") (pin "8") (pinfunction "8_8") (pintype "passive"))
      (node (ref "R2") (pin "1") (pinfunction "1_1") (pintype "passive"))
    )
    (net (code "49") (name "Net-(P2-Pad1)") (class "Default")
      (node (ref "P2") (pin "1") (pinfunction "1_1") (pintype "passive"))
      (node (ref "R18") (pin "1") (pinfunction "1_1") (pintype "passive"))
    )
    (net (code "50") (name "Net-(P2-Pad2)") (class "Default")
      (node (ref "P2") (pin "2") (pinfunction "2_2") (pintype "passive"))
      (node (ref "R17") (pin "1") (pinfunction "1_1") (pintype "passive"))
    )
    (net (code "51") (name "Net-(P2-Pad3)") (class "Default")
      (node (ref "P2") (pin "3") (pinfunction "3_3") (pintype "passive"))
      (node (ref "R16") (pin "1") (pinfunction "1_1") (pintype "passive"))
    )
    (net (code "52") (name "Net-(P2-Pad4)") (class "Default")
      (node (ref "P2") (pin "4") (pinfunction "4_4") (pintype "passive"))
      (node (ref "R15") (pin "1") (pinfunction "1_1") (pintype "passive"))
    )
    (net (code "53") (name "Net-(P2-Pad5)") (class "Default")
      (node (ref "P2") (pin "5") (pinfunction "5_5") (pintype "passive"))
      (node (ref "R14") (pin "1") (pinfunction "1_1") (pintype "passive"))
    )
    (net (code "54") (name "Net-(P2-Pad6)") (class "Default")
      (node (ref "P2") (pin "6") (pinfunction "6_6") (pintype "passive"))
      (node (ref "R13") (pin "1") (pinfunction "1_1") (pintype "passive"))
    )
    (net (code "55") (name "Net-(P2-Pad7)") (class "Default")
      (node (ref "P2") (pin "7") (pinfunction "7_7") (pintype "passive"))
      (node (ref "R12") (pin "1") (pinfunction "1_1") (pintype "passive"))
    )
    (net (code "56") (name "Net-(P2-Pad8)") (class "Default")
      (node (ref "P2") (pin "8") (pinfunction "8_8") (pintype "passive"))
      (node (ref "R11") (pin "1") (pinfunction "1_1") (pintype "passive"))
    )
    (net (code "57") (name "Net-(P12-Pad1)") (class "Default")
      (node (ref "P12") (pin "1") (pinfunction "1_1") (pintype "passive"))
      (node (ref "P5") (pin "1") (pinfunction "1_1") (pintype "passive"))
      (node (ref "R26") (pin "1") (pinfunction "1_1") (pintype "passive"))
    )
    (net (code "58") (name "Net-(P12-Pad2)") (class "Default")
      (node (ref "P12") (pin "2") (pinfunction "2_2") (pintype "passive"))
      (node (ref "P5") (pin "2") (pinfunction "2_2") (pintype "passive"))
      (node (ref "R25") (pin "1") (pinfunction "1_1") (pintype "passive"))
    )
    (net (code "59") (name "Net-(P12-Pad3)") (class "Default")
      (node (ref "P12") (pin "3") (pinfunction "3_3") (pintype "passive"))
      (node (ref "P5") (pin "3") (pinfunction "3_3") (pintype "passive"))
      (node (ref "R24") (pin "1") (pinfunction "1_1") (pintype "passive"))
    )
    (net (code "60") (name "Net-(P12-Pad4)") (class "Default")
      (node (ref "P12") (pin "4") (pinfunction "4_4") (pintype "passive"))
      (node (ref "P5") (pin "4") (pinfunction "4_4") (pintype "passive"))
      (node (ref "R23") (pin "1") (pinfunction "1_1") (pintype "passive"))
    )
    (net (code "61") (name "Net-(P12-Pad5)") (class "Default")
      (node (ref "P12") (pin "5") (pinfunction "5_5") (pintype "passive"))
      (node (ref "P5") (pin "5") (pinfunction "5_5") (pintype "passive"))
      (node (ref "R22") (pin "1") (pinfunction "1_1") (pintype "passive"))
    )
    (net (code "62") (name "Net-(P12-Pad6)") (class "Default")
      (node (ref "P12") (pin "6") (pinfunction "6_6") (pintype "passive"))
      (node (ref "P5") (pin "6") (pinfunction "6_6") (pintype "passive"))
      (node (ref "R21") (pin "1") (pinfunction "1_1") (pintype "passive"))
    )
    (net (code "63") (name "Net-(P12-Pad7)") (class "Default")
      (node (ref "P12") (pin "7") (pinfunction "7_7") (pintype "passive"))
      (node (ref "P5") (pin "7") (pinfunction "7_7") (pintype "passive"))
      (node (ref "R20") (pin "1") (pinfunction "1_1") (pintype "passive"))
    )
    (net (code "64") (name "Net-(P12-Pad8)") (class "Default")
      (node (ref "P12") (pin "8") (pinfunction "8_8") (pintype "passive"))
      (node (ref "P5") (pin "8") (pinfunction "8_8") (pintype "passive"))
      (node (ref "R19") (pin "1") (pinfunction "1_1") (pintype "passive"))
    )
    (net (code "65") (name "Net-(P19-Pad1)") (class "Default")
      (node (ref "P19") (pin "1") (pinfunction "1_1") (pintype "passive"))
      (node (ref "P19") (pin "2") (pinfunction "2_2") (pintype "passive"))
      (node (ref "R28") (pin "1") (pinfunction "1_1") (pintype "passive"))
    )
    (net (code "66") (name "Net-(P20-Pad1)") (class "Default")
      (node (ref "P20") (pin "1") (pinfunction "1_1") (pintype "passive"))
      (node (ref "P20") (pin "2") (pinfunction "2_2") (pintype "passive"))
      (node (ref "R29") (pin "2") (pinfunction "2_2") (pintype "passive"))
    )
    (net (code "67") (name "Net-(P21-Pad1)") (class "Default")
      (node (ref "P21") (pin "1") (pinfunction "1_1") (pintype "passive"))
      (node (ref "SS1") (pin "2") (pinfunction "2_2") (pintype "passive"))
    )
    (net (code "68") (name "Net-(P22-Pad1)") (class "Default")
      (node (ref "P22") (pin "1") (pinfunction "1_1") (pintype "passive"))
      (node (ref "P22") (pin "2") (pinfunction "2_2") (pintype "passive"))
      (node (ref "R31") (pin "1") (pinfunction "1_1") (pintype "passive"))
    )
    (net (code "69") (name "Net-(P24-Pad1)") (class "Default")
      (node (ref "P24") (pin "1") (pinfunction "1_1") (pintype "passive"))
      (node (ref "P24") (pin "2") (pinfunction "2_2") (pintype "passive"))
      (node (ref "R37") (pin "2") (pinfunction "2_2") (pintype "passive"))
    )
    (net (code "70") (name "Net-(P25-Pad1)") (class "Default")
      (node (ref "P25") (pin "1") (pinfunction "1_1") (pintype "passive"))
      (node (ref "P25") (pin "2") (pinfunction "2_2") (pintype "passive"))
      (node (ref "R34") (pin "2") (pinfunction "2_2") (pintype "passive"))
    )
    (net (code "71") (name "Net-(P26-Pad1)") (class "Default")
      (node (ref "P26") (pin "1") (pinfunction "1_1") (pintype "passive"))
      (node (ref "P26") (pin "2") (pinfunction "2_2") (pintype "passive"))
      (node (ref "R38") (pin "1") (pinfunction "1_1") (pintype "passive"))
    )
    (net (code "72") (name "Net-(P27-Pad1)") (class "Default")
      (node (ref "P27") (pin "1") (pinfunction "1_1") (pintype "passive"))
      (node (ref "P27") (pin "2") (pinfunction "2_2") (pintype "passive"))
      (node (ref "R39") (pin "1") (pinfunction "1_1") (pintype "passive"))
    )
    (net (code "73") (name "Net-(Q1-B)") (class "Default")
      (node (ref "Q1") (pin "2") (pinfunction "B_2") (pintype "passive"))
      (node (ref "R37") (pin "1") (pinfunction "1_1") (pintype "passive"))
      (node (ref "R40") (pin "2") (pinfunction "2_2") (pintype "passive"))
    )
    (net (code "74") (name "Net-(Q1-C)") (class "Default")
      (node (ref "BUZ1") (pin "N") (pinfunction "N_N") (pintype "passive"))
      (node (ref "Q1") (pin "1") (pinfunction "C_1") (pintype "passive"))
    )
    (net (code "75") (name "Net-(R1-WIPER)") (class "Default")
      (node (ref "R1") (pin "2") (pinfunction "WIPER_2") (pintype "passive"))
      (node (ref "R38") (pin "2") (pinfunction "2_2") (pintype "passive"))
    )
    (net (code "76") (name "Net-(R29-Pad1)") (class "Default")
      (node (ref "R29") (pin "1") (pinfunction "1_1") (pintype "passive"))
      (node (ref "U11") (pin "OUT") (pinfunction "OUT_OUT") (pintype "bidirectional"))
    )
    (net (code "77") (name "Net-(R32-WIPER)") (class "Default")
      (node (ref "R32") (pin "2") (pinfunction "WIPER_2") (pintype "passive"))
      (node (ref "R39") (pin "2") (pinfunction "2_2") (pintype "passive"))
    )
    (net (code "78") (name "Net-(U12-VOUT)") (class "Default")
      (node (ref "R28") (pin "2") (pinfunction "2_2") (pintype "passive"))
      (node (ref "U12") (pin "2") (pinfunction "VOUT_2") (pintype "output"))
    )
    (net (code "79") (name "Net-(U13-C1+)") (class "Default")
      (node (ref "C17") (pin "1") (pinfunction "1_1") (pintype "passive"))
      (node (ref "U13") (pin "1") (pinfunction "C1+_1") (pintype "bidirectional"))
    )
    (net (code "80") (name "Net-(U13-C1-)") (class "Default")
      (node (ref "C17") (pin "2") (pinfunction "2_2") (pintype "passive"))
      (node (ref "U13") (pin "3") (pinfunction "C1-_3") (pintype "bidirectional"))
    )
    (net (code "81") (name "Net-(U13-C2+)") (class "Default")
      (node (ref "C18") (pin "1") (pinfunction "1_1") (pintype "passive"))
      (node (ref "U13") (pin "4") (pinfunction "C2+_4") (pintype "bidirectional"))
    )
    (net (code "82") (name "Net-(U13-C2-)") (class "Default")
      (node (ref "C18") (pin "2") (pinfunction "2_2") (pintype "passive"))
      (node (ref "U13") (pin "5") (pinfunction "C2-_5") (pintype "bidirectional"))
    )
    (net (code "83") (name "Net-(U13-R2IN)") (class "Default")
      (node (ref "R30") (pin "2") (pinfunction "2_2") (pintype "passive"))
      (node (ref "U13") (pin "8") (pinfunction "R2IN_8") (pintype "input"))
    )
    (net (code "84") (name "Net-(U13-R2OUT)") (class "Default")
      (node (ref "R34") (pin "1") (pinfunction "1_1") (pintype "passive"))
      (node (ref "U13") (pin "9") (pinfunction "R2OUT_9") (pintype "output"))
    )
    (net (code "85") (name "Net-(U13-T2IN)") (class "Default")
      (node (ref "R31") (pin "2") (pinfunction "2_2") (pintype "passive"))
      (node (ref "U13") (pin "10") (pinfunction "T2IN_10") (pintype "input"))
    )
    (net (code "86") (name "Net-(U13-T2OUT)") (class "Default")
      (node (ref "R36") (pin "1") (pinfunction "1_1") (pintype "passive"))
      (node (ref "U13") (pin "7") (pinfunction "T2OUT_7") (pintype "output"))
    )
    (net (code "87") (name "Net-(U13-VS+)") (class "Default")
      (node (ref "C12") (pin "1") (pinfunction "1_1") (pintype "passive"))
      (node (ref "U13") (pin "2") (pinfunction "VS+_2") (pintype "power_in"))
    )
    (net (code "88") (name "Net-(U13-VS-)") (class "Default")
      (node (ref "C15") (pin "1") (pinfunction "1_1") (pintype "passive"))
      (node (ref "U13") (pin "6") (pinfunction "VS-_6") (pintype "power_in"))
    )
    (net (code "89") (name "Net-(Y1-OSC1)") (class "Default")
      (node (ref "C6") (pin "1") (pinfunction "1_1") (pintype "passive"))
      (node (ref "SS1") (pin "1") (pinfunction "1_1") (pintype "passive"))
      (node (ref "Y1") (pin "1") (pinfunction "OSC1_1") (pintype "passive"))
    )
    (net (code "90") (name "Net-(Y1-OSC2)") (class "Default")
      (node (ref "C9") (pin "1") (pinfunction "1_1") (pintype "passive"))
      (node (ref "P21") (pin "2") (pinfunction "2_2") (pintype "passive"))
      (node (ref "Y1") (pin "2") (pinfunction "OSC2_2") (pintype "passive"))
    )
    (net (code "91") (name "OSC11") (class "Default")
      (node (ref "P11") (pin "2") (pinfunction "2_2") (pintype "passive"))
      (node (ref "U5") (pin "26") (pinfunction "OSC1_26") (pintype "passive"))
      (node (ref "U6") (pin "15") (pinfunction "OSC2_15") (pintype "passive"))
    )
    (net (code "92") (name "OSC21") (class "Default")
      (node (ref "P11") (pin "3") (pinfunction "3_3") (pintype "passive"))
      (node (ref "U5") (pin "27") (pinfunction "OSC2_27") (pintype "passive"))
      (node (ref "U6") (pin "16") (pinfunction "OSC1_16") (pintype "passive"))
    )
    (net (code "93") (name "RA0") (class "Default")
      (node (ref "P4") (pin "2") (pinfunction "2_2") (pintype "passive"))
      (node (ref "P6") (pin "1") (pinfunction "1_1") (pintype "passive"))
      (node (ref "U10") (pin "5") (pinfunction "GP0_5") (pintype "passive"))
      (node (ref "U3") (pin "2") (pinfunction "RA0/AN0_2") (pintype "passive"))
      (node (ref "U4") (pin "19") (pinfunction "RA0/AN0_19") (pintype "passive"))
      (node (ref "U5") (pin "6") (pinfunction "RA0_6") (pintype "passive"))
      (node (ref "U6") (pin "17") (pinfunction "RA0_17") (pintype "passive"))
      (node (ref "U7") (pin "7") (pinfunction "GP0_7") (pintype "passive"))
      (node (ref "U8") (pin "13") (pinfunction "RA0/ICSPDAT_13") (pintype "passive"))
      (node (ref "U9") (pin "2") (pinfunction "RA0/AN0_2") (pintype "passive"))
    )
    (net (code "94") (name "RA1") (class "Default")
      (node (ref "P4") (pin "3") (pinfunction "3_3") (pintype "passive"))
      (node (ref "P6") (pin "2") (pinfunction "2_2") (pintype "passive"))
      (node (ref "U10") (pin "4") (pinfunction "GP1_4") (pintype "passive"))
      (node (ref "U3") (pin "3") (pinfunction "RA1/AN1_3") (pintype "passive"))
      (node (ref "U4") (pin "18") (pinfunction "RA1/AN1_18") (pintype "passive"))
      (node (ref "U5") (pin "7") (pinfunction "RA1_7") (pintype "passive"))
      (node (ref "U6") (pin "18") (pinfunction "RA1_18") (pintype "passive"))
      (node (ref "U7") (pin "6") (pinfunction "GP2_6") (pintype "passive"))
      (node (ref "U8") (pin "12") (pinfunction "RA1/ICSPCLK_12") (pintype "passive"))
      (node (ref "U9") (pin "3") (pinfunction "RA1/AN1_3") (pintype "passive"))
    )
    (net (code "95") (name "RA2") (class "Default")
      (node (ref "P4") (pin "4") (pinfunction "4_4") (pintype "passive"))
      (node (ref "P6") (pin "3") (pinfunction "3_3") (pintype "passive"))
      (node (ref "U10") (pin "3") (pinfunction "GP2_3") (pintype "passive"))
      (node (ref "U3") (pin "4") (pinfunction "RA2/AN2_4") (pintype "passive"))
      (node (ref "U4") (pin "17") (pinfunction "RA2/AN2_17") (pintype "passive"))
      (node (ref "U5") (pin "8") (pinfunction "RA2_8") (pintype "passive"))
      (node (ref "U6") (pin "1") (pinfunction "RA2_1") (pintype "passive"))
      (node (ref "U7") (pin "5") (pinfunction "GP2/T0CKI_5") (pintype "passive"))
      (node (ref "U8") (pin "11") (pinfunction "RA2/T0CKI_11") (pintype "passive"))
      (node (ref "U9") (pin "4") (pinfunction "RA2/AN2_4") (pintype "passive"))
    )
    (net (code "96") (name "RA3") (class "Default")
      (node (ref "P4") (pin "5") (pinfunction "5_5") (pintype "passive"))
      (node (ref "P6") (pin "4") (pinfunction "4_4") (pintype "passive"))
      (node (ref "U3") (pin "5") (pinfunction "RA3/AN3_5") (pintype "passive"))
      (node (ref "U5") (pin "9") (pinfunction "RA3_9") (pintype "passive"))
      (node (ref "U6") (pin "2") (pinfunction "RA3_2") (pintype "passive"))
      (node (ref "U9") (pin "5") (pinfunction "RA3/AN3_5") (pintype "passive"))
    )
    (net (code "97") (name "RA4") (class "Default")
      (node (ref "P4") (pin "6") (pinfunction "6_6") (pintype "passive"))
      (node (ref "P6") (pin "5") (pinfunction "5_5") (pintype "passive"))
      (node (ref "U3") (pin "6") (pinfunction "RA4/T0CKI_6") (pintype "passive"))
      (node (ref "U4") (pin "3") (pinfunction "RA4/AN3_3") (pintype "passive"))
      (node (ref "U6") (pin "3") (pinfunction "RA4/T0CKI_3") (pintype "passive"))
      (node (ref "U7") (pin "3") (pinfunction "GP4/OSC2_3") (pintype "passive"))
      (node (ref "U8") (pin "3") (pinfunction "RA4/OSC2_3") (pintype "passive"))
      (node (ref "U9") (pin "6") (pinfunction "RA4/T0CKI_6") (pintype "passive"))
    )
    (net (code "98") (name "RA5") (class "Default")
      (node (ref "P4") (pin "7") (pinfunction "7_7") (pintype "passive"))
      (node (ref "P6") (pin "6") (pinfunction "6_6") (pintype "passive"))
      (node (ref "U3") (pin "7") (pinfunction "RA5/AN4/SS_7") (pintype "passive"))
      (node (ref "U4") (pin "2") (pinfunction "RA5/T1CKI_2") (pintype "passive"))
      (node (ref "U7") (pin "2") (pinfunction "GP5/OSC1_2") (pintype "passive"))
      (node (ref "U8") (pin "2") (pinfunction "RA5/OSC1_2") (pintype "passive"))
      (node (ref "U9") (pin "7") (pinfunction "RA5/AN4/SS_7") (pintype "passive"))
    )
    (net (code "99") (name "RA6") (class "Default")
      (node (ref "P4") (pin "12") (pinfunction "12_12") (pintype "passive"))
      (node (ref "P6") (pin "7") (pinfunction "7_7") (pintype "passive"))
      (node (ref "U3") (pin "14") (pinfunction "RA6/OSC2_14") (pintype "passive"))
      (node (ref "U9") (pin "10") (pinfunction "RA6/OSC2_10") (pintype "passive"))
    )
    (net (code "100") (name "RA7") (class "Default")
      (node (ref "P4") (pin "11") (pinfunction "11_11") (pintype "passive"))
      (node (ref "P6") (pin "8") (pinfunction "8_8") (pintype "passive"))
      (node (ref "U3") (pin "13") (pinfunction "RA7/OSC1_13") (pintype "passive"))
      (node (ref "U9") (pin "9") (pinfunction "RA7/OSC1_9") (pintype "passive"))
    )
    (net (code "101") (name "RB0") (class "Default")
      (node (ref "P50") (pin "11") (pinfunction "11_11") (pintype "passive"))
      (node (ref "P7") (pin "1") (pinfunction "1_1") (pintype "passive"))
      (node (ref "U3") (pin "33") (pinfunction "RB0/AN12_33") (pintype "passive"))
      (node (ref "U5") (pin "10") (pinfunction "RB0_10") (pintype "passive"))
      (node (ref "U6") (pin "6") (pinfunction "RB0/INT_6") (pintype "passive"))
      (node (ref "U9") (pin "21") (pinfunction "RB0/AN12_21") (pintype "passive"))
    )
    (net (code "102") (name "RB1") (class "Default")
      (node (ref "P50") (pin "12") (pinfunction "12_12") (pintype "passive"))
      (node (ref "P7") (pin "2") (pinfunction "2_2") (pintype "passive"))
      (node (ref "U3") (pin "34") (pinfunction "RB1/AN10_34") (pintype "passive"))
      (node (ref "U5") (pin "11") (pinfunction "RB1_11") (pintype "passive"))
      (node (ref "U6") (pin "7") (pinfunction "RB1_7") (pintype "passive"))
      (node (ref "U9") (pin "22") (pinfunction "RB1/AN10_22") (pintype "passive"))
    )
    (net (code "103") (name "RB2") (class "Default")
      (node (ref "P50") (pin "13") (pinfunction "13_13") (pintype "passive"))
      (node (ref "P7") (pin "3") (pinfunction "3_3") (pintype "passive"))
      (node (ref "U3") (pin "35") (pinfunction "RB2/AN8_35") (pintype "passive"))
      (node (ref "U5") (pin "12") (pinfunction "RB2_12") (pintype "passive"))
      (node (ref "U6") (pin "8") (pinfunction "RB2_8") (pintype "passive"))
      (node (ref "U9") (pin "23") (pinfunction "RB2/AN8_23") (pintype "passive"))
    )
    (net (code "104") (name "RB3") (class "Default")
      (node (ref "P50") (pin "14") (pinfunction "14_14") (pintype "passive"))
      (node (ref "P7") (pin "4") (pinfunction "4_4") (pintype "passive"))
      (node (ref "U3") (pin "36") (pinfunction "RB3/AN9_36") (pintype "passive"))
      (node (ref "U5") (pin "13") (pinfunction "RB3_13") (pintype "passive"))
      (node (ref "U6") (pin "9") (pinfunction "RB3_9") (pintype "passive"))
      (node (ref "U9") (pin "24") (pinfunction "RB3/AN9_24") (pintype "passive"))
    )
    (net (code "105") (name "RB4") (class "Default")
      (node (ref "P50") (pin "15") (pinfunction "15_15") (pintype "passive"))
      (node (ref "P7") (pin "5") (pinfunction "5_5") (pintype "passive"))
      (node (ref "U3") (pin "37") (pinfunction "RB4/AN11_37") (pintype "passive"))
      (node (ref "U4") (pin "13") (pinfunction "RB4/AN10_13") (pintype "passive"))
      (node (ref "U5") (pin "14") (pinfunction "RB4_14") (pintype "passive"))
      (node (ref "U6") (pin "10") (pinfunction "RB4_10") (pintype "passive"))
      (node (ref "U9") (pin "25") (pinfunction "RB4/AN11_25") (pintype "passive"))
    )
    (net (code "106") (name "RB5") (class "Default")
      (node (ref "P50") (pin "16") (pinfunction "16_16") (pintype "passive"))
      (node (ref "P7") (pin "6") (pinfunction "6_6") (pintype "passive"))
      (node (ref "U3") (pin "38") (pinfunction "RB5/AN13_38") (pintype "passive"))
      (node (ref "U4") (pin "12") (pinfunction "RB5/AN11/RX_12") (pintype "passive"))
      (node (ref "U5") (pin "15") (pinfunction "RB5_15") (pintype "passive"))
      (node (ref "U6") (pin "11") (pinfunction "RB5_11") (pintype "passive"))
      (node (ref "U9") (pin "26") (pinfunction "RB5/AN13_26") (pintype "passive"))
    )
    (net (code "107") (name "RB6") (class "Default")
      (node (ref "P23") (pin "1") (pinfunction "1_1") (pintype "passive"))
      (node (ref "P50") (pin "17") (pinfunction "17_17") (pintype "passive"))
      (node (ref "P7") (pin "7") (pinfunction "7_7") (pintype "passive"))
      (node (ref "U3") (pin "39") (pinfunction "RB6/ICSPCLK_39") (pintype "passive"))
      (node (ref "U4") (pin "11") (pinfunction "RB6_11") (pintype "passive"))
      (node (ref "U5") (pin "16") (pinfunction "RB6/ICSPCLK_16") (pintype "passive"))
      (node (ref "U6") (pin "12") (pinfunction "RB6/ICSPCLK_12") (pintype "passive"))
      (node (ref "U9") (pin "27") (pinfunction "RB6/ICSPCLK_27") (pintype "passive"))
    )
    (net (code "108") (name "RB7") (class "Default")
      (node (ref "P23") (pin "2") (pinfunction "2_2") (pintype "passive"))
      (node (ref "P50") (pin "18") (pinfunction "18_18") (pintype "passive"))
      (node (ref "P7") (pin "8") (pinfunction "8_8") (pintype "passive"))
      (node (ref "U3") (pin "40") (pinfunction "RB7/ICSPDAT_40") (pintype "passive"))
      (node (ref "U4") (pin "10") (pinfunction "RB7/TX_10") (pintype "passive"))
      (node (ref "U5") (pin "17") (pinfunction "RB7/ICSPDAT_17") (pintype "passive"))
      (node (ref "U6") (pin "13") (pinfunction "RB7/ICSPDAT_13") (pintype "passive"))
      (node (ref "U9") (pin "28") (pinfunction "RB7/ICSPDAT_28") (pintype "passive"))
    )
    (net (code "109") (name "RC0") (class "Default")
      (node (ref "P4") (pin "13") (pinfunction "13_13") (pintype "passive"))
      (node (ref "P8") (pin "1") (pinfunction "1_1") (pintype "passive"))
      (node (ref "U3") (pin "15") (pinfunction "RC0/T1OSO/T1CKI_15") (pintype "passive"))
      (node (ref "U4") (pin "16") (pinfunction "RC0/AN4_16") (pintype "passive"))
      (node (ref "U5") (pin "18") (pinfunction "RC0_18") (pintype "passive"))
      (node (ref "U8") (pin "10") (pinfunction "RC0_10") (pintype "passive"))
      (node (ref "U9") (pin "11") (pinfunction "RC0/T1OSO/T1CKI_11") (pintype "passive"))
    )
    (net (code "110") (name "RC1") (class "Default")
      (node (ref "P4") (pin "14") (pinfunction "14_14") (pintype "passive"))
      (node (ref "P8") (pin "2") (pinfunction "2_2") (pintype "passive"))
      (node (ref "U3") (pin "16") (pinfunction "RC1/T1OSI/CCP2_16") (pintype "passive"))
      (node (ref "U4") (pin "15") (pinfunction "RC1/AN5_15") (pintype "passive"))
      (node (ref "U5") (pin "19") (pinfunction "RC1_19") (pintype "passive"))
      (node (ref "U8") (pin "9") (pinfunction "RC1_9") (pintype "passive"))
      (node (ref "U9") (pin "12") (pinfunction "RC1/T1OSI/CCP2_12") (pintype "passive"))
    )
    (net (code "111") (name "RC2") (class "Default")
      (node (ref "P4") (pin "15") (pinfunction "15_15") (pintype "passive"))
      (node (ref "P8") (pin "3") (pinfunction "3_3") (pintype "passive"))
      (node (ref "U3") (pin "17") (pinfunction "RC2/CCP1_17") (pintype "passive"))
      (node (ref "U4") (pin "14") (pinfunction "RC2/AN6_14") (pintype "passive"))
      (node (ref "U5") (pin "20") (pinfunction "RC2_20") (pintype "passive"))
      (node (ref "U8") (pin "8") (pinfunction "RC2_8") (pintype "passive"))
      (node (ref "U9") (pin "13") (pinfunction "RC2/CCP1_13") (pintype "passive"))
    )
    (net (code "112") (name "RC3") (class "Default")
      (node (ref "P4") (pin "16") (pinfunction "16_16") (pintype "passive"))
      (node (ref "P8") (pin "4") (pinfunction "4_4") (pintype "passive"))
      (node (ref "U3") (pin "18") (pinfunction "RC3/SCK/SCL_18") (pintype "passive"))
      (node (ref "U4") (pin "7") (pinfunction "RC3/AN7_7") (pintype "passive"))
      (node (ref "U5") (pin "21") (pinfunction "RC3_21") (pintype "passive"))
      (node (ref "U8") (pin "7") (pinfunction "RC3_7") (pintype "passive"))
      (node (ref "U9") (pin "14") (pinfunction "RC3/SCK/SCL_14") (pintype "passive"))
    )
    (net (code "113") (name "RC4") (class "Default")
      (node (ref "P50") (pin "3") (pinfunction "3_3") (pintype "passive"))
      (node (ref "P8") (pin "5") (pinfunction "5_5") (pintype "passive"))
      (node (ref "U3") (pin "23") (pinfunction "RC4/SDI/SDA_23") (pintype "passive"))
      (node (ref "U4") (pin "6") (pinfunction "RC4_6") (pintype "passive"))
      (node (ref "U5") (pin "22") (pinfunction "RC4_22") (pintype "passive"))
      (node (ref "U8") (pin "6") (pinfunction "RC4_6") (pintype "passive"))
      (node (ref "U9") (pin "15") (pinfunction "RC4/SDI/SDA_15") (pintype "passive"))
    )
    (net (code "114") (name "RC5") (class "Default")
      (node (ref "P50") (pin "4") (pinfunction "4_4") (pintype "passive"))
      (node (ref "P8") (pin "6") (pinfunction "6_6") (pintype "passive"))
      (node (ref "U3") (pin "24") (pinfunction "RC5/SDO_24") (pintype "passive"))
      (node (ref "U4") (pin "5") (pinfunction "RC5/CCP1_5") (pintype "passive"))
      (node (ref "U5") (pin "23") (pinfunction "RC5_23") (pintype "passive"))
      (node (ref "U8") (pin "5") (pinfunction "RC5_5") (pintype "passive"))
      (node (ref "U9") (pin "16") (pinfunction "RC5/SDO_16") (pintype "passive"))
    )
    (net (code "115") (name "RC6") (class "Default")
      (node (ref "P50") (pin "5") (pinfunction "5_5") (pintype "passive"))
      (node (ref "P8") (pin "7") (pinfunction "7_7") (pintype "passive"))
      (node (ref "U3") (pin "25") (pinfunction "RC6/TX_25") (pintype "passive"))
      (node (ref "U4") (pin "8") (pinfunction "RC6/AN8/SS_8") (pintype "passive"))
      (node (ref "U5") (pin "24") (pinfunction "RC6_24") (pintype "passive"))
      (node (ref "U9") (pin "17") (pinfunction "RC6/TX_17") (pintype "passive"))
    )
    (net (code "116") (name "RC7") (class "Default")
      (node (ref "P50") (pin "6") (pinfunction "6_6") (pintype "passive"))
      (node (ref "P8") (pin "8") (pinfunction "8_8") (pintype "passive"))
      (node (ref "U3") (pin "26") (pinfunction "RC7/RX_26") (pintype "passive"))
      (node (ref "U4") (pin "9") (pinfunction "RC7/AN9/SDO_9") (pintype "passive"))
      (node (ref "U5") (pin "25") (pinfunction "RC7_25") (pintype "passive"))
      (node (ref "U9") (pin "18") (pinfunction "RC7/RX_18") (pintype "passive"))
    )
    (net (code "117") (name "RD0") (class "Default")
      (node (ref "P4") (pin "17") (pinfunction "17_17") (pintype "passive"))
      (node (ref "P9") (pin "1") (pinfunction "1_1") (pintype "passive"))
      (node (ref "U3") (pin "19") (pinfunction "RD0_19") (pintype "passive"))
    )
    (net (code "118") (name "RD1") (class "Default")
      (node (ref "P4") (pin "18") (pinfunction "18_18") (pintype "passive"))
      (node (ref "P9") (pin "2") (pinfunction "2_2") (pintype "passive"))
      (node (ref "U3") (pin "20") (pinfunction "RD1_20") (pintype "passive"))
    )
    (net (code "119") (name "RD2") (class "Default")
      (node (ref "P50") (pin "1") (pinfunction "1_1") (pintype "passive"))
      (node (ref "P9") (pin "3") (pinfunction "3_3") (pintype "passive"))
      (node (ref "U3") (pin "21") (pinfunction "RD2_21") (pintype "passive"))
    )
    (net (code "120") (name "RD3") (class "Default")
      (node (ref "P50") (pin "2") (pinfunction "2_2") (pintype "passive"))
      (node (ref "P9") (pin "4") (pinfunction "4_4") (pintype "passive"))
      (node (ref "U3") (pin "22") (pinfunction "RD3_22") (pintype "passive"))
    )
    (net (code "121") (name "RD4") (class "Default")
      (node (ref "P50") (pin "7") (pinfunction "7_7") (pintype "passive"))
      (node (ref "P9") (pin "5") (pinfunction "5_5") (pintype "passive"))
      (node (ref "U3") (pin "27") (pinfunction "RD4_27") (pintype "passive"))
    )
    (net (code "122") (name "RD5") (class "Default")
      (node (ref "P50") (pin "8") (pinfunction "8_8") (pintype "passive"))
      (node (ref "P9") (pin "6") (pinfunction "6_6") (pintype "passive"))
      (node (ref "U3") (pin "28") (pinfunction "RD5/P1B_28") (pintype "passive"))
    )
    (net (code "123") (name "RD6") (class "Default")
      (node (ref "P50") (pin "9") (pinfunction "9_9") (pintype "passive"))
      (node (ref "P9") (pin "7") (pinfunction "7_7") (pintype "passive"))
      (node (ref "U3") (pin "29") (pinfunction "RD6/P1C_29") (pintype "passive"))
    )
    (net (code "124") (name "RD7") (class "Default")
      (node (ref "P50") (pin "10") (pinfunction "10_10") (pintype "passive"))
      (node (ref "P9") (pin "8") (pinfunction "8_8") (pintype "passive"))
      (node (ref "U3") (pin "30") (pinfunction "RD7/P1D_30") (pintype "passive"))
    )
    (net (code "125") (name "RE0") (class "Default")
      (node (ref "P10") (pin "1") (pinfunction "1_1") (pintype "passive"))
      (node (ref "P4") (pin "8") (pinfunction "8_8") (pintype "passive"))
      (node (ref "U3") (pin "8") (pinfunction "RE0/AN5_8") (pintype "passive"))
    )
    (net (code "126") (name "RE1") (class "Default")
      (node (ref "P10") (pin "2") (pinfunction "2_2") (pintype "passive"))
      (node (ref "P4") (pin "9") (pinfunction "9_9") (pintype "passive"))
      (node (ref "U3") (pin "9") (pinfunction "RE1/AN6_9") (pintype "passive"))
    )
    (net (code "127") (name "RE2") (class "Default")
      (node (ref "P10") (pin "3") (pinfunction "3_3") (pintype "passive"))
      (node (ref "P4") (pin "10") (pinfunction "10_10") (pintype "passive"))
      (node (ref "U3") (pin "10") (pinfunction "RE2/AN7_10") (pintype "passive"))
    )
    (net (code "128") (name "Rx") (class "Default")
      (node (ref "J2") (pin "3") (pinfunction "3_3") (pintype "passive"))
      (node (ref "R30") (pin "1") (pinfunction "1_1") (pintype "passive"))
    )
    (net (code "129") (name "T0CKI") (class "Default")
      (node (ref "P11") (pin "1") (pinfunction "1_1") (pintype "passive"))
      (node (ref "U5") (pin "1") (pinfunction "TOCKI_1") (pintype "passive"))
    )
    (net (code "130") (name "Tx") (class "Default")
      (node (ref "J2") (pin "2") (pinfunction "2_2") (pintype "passive"))
      (node (ref "R36") (pin "2") (pinfunction "2_2") (pintype "passive"))
    )
    (net (code "131") (name "VCC") (class "Default")
      (node (ref "BUZ1") (pin "P") (pinfunction "P_P") (pintype "passive"))
      (node (ref "C11") (pin "2") (pinfunction "2_2") (pintype "passive"))
      (node (ref "C12") (pin "2") (pinfunction "2_2") (pintype "passive"))
      (node (ref "C13") (pin "2") (pinfunction "2_2") (pintype "passive"))
      (node (ref "C14") (pin "2") (pinfunction "2_2") (pintype "passive"))
      (node (ref "C16") (pin "2") (pinfunction "2_2") (pintype "passive"))
      (node (ref "C2") (pin "2") (pinfunction "2_2") (pintype "passive"))
      (node (ref "C4") (pin "1") (pinfunction "1_1") (pintype "passive"))
      (node (ref "C5") (pin "2") (pinfunction "2_2") (pintype "passive"))
      (node (ref "C7") (pin "2") (pinfunction "2_2") (pintype "passive"))
      (node (ref "C8") (pin "1") (pinfunction "1_1") (pintype "passive"))
      (node (ref "P23") (pin "4") (pinfunction "4_4") (pintype "passive"))
      (node (ref "R1") (pin "1") (pinfunction "CCW_1") (pintype "passive"))
      (node (ref "R27") (pin "2") (pinfunction "2_2") (pintype "passive"))
      (node (ref "R32") (pin "1") (pinfunction "CCW_1") (pintype "passive"))
      (node (ref "R35") (pin "2") (pinfunction "2_2") (pintype "passive"))
      (node (ref "R5") (pin "2") (pinfunction "2_2") (pintype "passive"))
      (node (ref "U10") (pin "2") (pinfunction "Vdd_2") (pintype "passive"))
      (node (ref "U11") (pin "VCC") (pinfunction "V+_VCC") (pintype "bidirectional"))
      (node (ref "U12") (pin "1") (pinfunction "+VS_1") (pintype "power_in"))
      (node (ref "U13") (pin "16") (pinfunction "VCC_16") (pintype "power_in"))
      (node (ref "U2") (pin "3") (pinfunction "OUTPUT_3") (pintype "passive"))
      (node (ref "U3") (pin "11") (pinfunction "Vdd_11") (pintype "passive"))
      (node (ref "U3") (pin "32") (pinfunction "Vdd_32") (pintype "passive"))
      (node (ref "U4") (pin "1") (pinfunction "Vdd_1") (pintype "passive"))
      (node (ref "U5") (pin "2") (pinfunction "Vdd_2") (pintype "passive"))
      (node (ref "U6") (pin "14") (pinfunction "Vdd_14") (pintype "passive"))
      (node (ref "U8") (pin "1") (pinfunction "Vdd_1") (pintype "passive"))
      (node (ref "U9") (pin "20") (pinfunction "Vdd_20") (pintype "passive"))
    )
    (net (code "132") (name "i1") (class "Default")
      (node (ref "P42") (pin "1") (pinfunction "1_1") (pintype "passive"))
      (node (ref "U1") (pin "1") (pinfunction "I1_1") (pintype "input"))
    )
    (net (code "133") (name "i2") (class "Default")
      (node (ref "P42") (pin "2") (pinfunction "2_2") (pintype "passive"))
      (node (ref "U1") (pin "2") (pinfunction "I2_2") (pintype "input"))
    )
    (net (code "134") (name "reset") (class "Default")
      (node (ref "C19") (pin "2") (pinfunction "2_2") (pintype "passive"))
      (node (ref "P23") (pin "5") (pinfunction "5_5") (pintype "passive"))
      (node (ref "P4") (pin "1") (pinfunction "1_1") (pintype "passive"))
      (node (ref "R35") (pin "1") (pinfunction "1_1") (pintype "passive"))
      (node (ref "S1") (pin "3") (pinfunction "3_3") (pintype "passive"))
      (node (ref "S1") (pin "4") (pinfunction "4_4") (pintype "passive"))
      (node (ref "U10") (pin "8") (pinfunction "GP3/MCLR_8") (pintype "passive"))
      (node (ref "U3") (pin "1") (pinfunction "MCLR/VPP_1") (pintype "passive"))
      (node (ref "U4") (pin "4") (pinfunction "RA3/MCLR_4") (pintype "passive"))
      (node (ref "U5") (pin "28") (pinfunction "MCLR_28") (pintype "passive"))
      (node (ref "U6") (pin "4") (pinfunction "MCLR_4") (pintype "passive"))
      (node (ref "U7") (pin "4") (pinfunction "MCLR_4") (pintype "passive"))
      (node (ref "U8") (pin "4") (pinfunction "RA3/MCLR_4") (pintype "passive"))
      (node (ref "U9") (pin "1") (pinfunction "MCLR_1") (pintype "passive"))
    )
    (net (code "135") (name "unconnected-(J2-Pad1)") (class "Default")
      (node (ref "J2") (pin "1") (pinfunction "1_1") (pintype "passive"))
    )
    (net (code "136") (name "unconnected-(J2-Pad4)") (class "Default")
      (node (ref "J2") (pin "4") (pinfunction "4_4") (pintype "passive"))
    )
    (net (code "137") (name "unconnected-(J2-Pad5)") (class "Default")
      (node (ref "J2") (pin "5") (pinfunction "5_5") (pintype "passive"))
    )
    (net (code "138") (name "unconnected-(J2-Pad6)") (class "Default")
      (node (ref "J2") (pin "6") (pinfunction "6_6") (pintype "passive"))
    )
    (net (code "139") (name "unconnected-(J2-Pad7)") (class "Default")
      (node (ref "J2") (pin "7") (pinfunction "7_7") (pintype "passive"))
    )
    (net (code "140") (name "unconnected-(J2-Pad8)") (class "Default")
      (node (ref "J2") (pin "8") (pinfunction "8_8") (pintype "passive"))
    )
    (net (code "141") (name "unconnected-(J2-Pad9)") (class "Default")
      (node (ref "J2") (pin "9") (pinfunction "9_9") (pintype "passive"))
    )
    (net (code "142") (name "unconnected-(U1-CD+-Pad9)") (class "Default")
      (node (ref "U1") (pin "9") (pinfunction "CD+_9") (pintype "passive"))
    )
    (net (code "143") (name "unconnected-(U1-GND-Pad8)") (class "Default")
      (node (ref "U1") (pin "8") (pinfunction "GND_8") (pintype "power_in"))
    )
    (net (code "144") (name "unconnected-(U1-I3-Pad3)") (class "Default")
      (node (ref "U1") (pin "3") (pinfunction "I3_3") (pintype "input"))
    )
    (net (code "145") (name "unconnected-(U1-I4-Pad4)") (class "Default")
      (node (ref "U1") (pin "4") (pinfunction "I4_4") (pintype "input"))
    )
    (net (code "146") (name "unconnected-(U1-I5-Pad5)") (class "Default")
      (node (ref "U1") (pin "5") (pinfunction "I5_5") (pintype "input"))
    )
    (net (code "147") (name "unconnected-(U1-I6-Pad6)") (class "Default")
      (node (ref "U1") (pin "6") (pinfunction "I6_6") (pintype "input"))
    )
    (net (code "148") (name "unconnected-(U1-I7-Pad7)") (class "Default")
      (node (ref "U1") (pin "7") (pinfunction "I7_7") (pintype "input"))
    )
    (net (code "149") (name "unconnected-(U1-O3-Pad14)") (class "Default")
      (node (ref "U1") (pin "14") (pinfunction "O3_14") (pintype "open_collector"))
    )
    (net (code "150") (name "unconnected-(U1-O4-Pad13)") (class "Default")
      (node (ref "U1") (pin "13") (pinfunction "O4_13") (pintype "open_collector"))
    )
    (net (code "151") (name "unconnected-(U1-O5-Pad12)") (class "Default")
      (node (ref "U1") (pin "12") (pinfunction "O5_12") (pintype "open_collector"))
    )
    (net (code "152") (name "unconnected-(U1-O6-Pad11)") (class "Default")
      (node (ref "U1") (pin "11") (pinfunction "O6_11") (pintype "open_collector"))
    )
    (net (code "153") (name "unconnected-(U1-O7-Pad10)") (class "Default")
      (node (ref "U1") (pin "10") (pinfunction "O7_10") (pintype "open_collector"))
    )
    (net (code "154") (name "unconnected-(U5-NC-Pad3)") (class "Default")
      (node (ref "U5") (pin "3") (pinfunction "NC_3") (pintype "passive"))
    )
    (net (code "155") (name "unconnected-(U5-NC-Pad5)") (class "Default")
      (node (ref "U5") (pin "5") (pinfunction "NC_5") (pintype "passive"))
    )
    (net (code "156") (name "unconnected-(U10-NC-Pad1)") (class "Default")
      (node (ref "U10") (pin "1") (pinfunction "NC_1") (pintype "passive"))
    )
    (net (code "157") (name "unconnected-(U10-NC-Pad6)") (class "Default")
      (node (ref "U10") (pin "6") (pinfunction "NC_6") (pintype "passive"))
    )
    (net (code "158") (name "unconnected-(U13-R1IN-Pad13)") (class "Default")
      (node (ref "U13") (pin "13") (pinfunction "R1IN_13") (pintype "input"))
    )
    (net (code "159") (name "unconnected-(U13-R1OUT-Pad12)") (class "Default")
      (node (ref "U13") (pin "12") (pinfunction "R1OUT_12") (pintype "output"))
    )
    (net (code "160") (name "unconnected-(U13-T1IN-Pad11)") (class "Default")
      (node (ref "U13") (pin "11") (pinfunction "T1IN_11") (pintype "input"))
    )
    (net (code "161") (name "unconnected-(U13-T1OUT-Pad14)") (class "Default")
      (node (ref "U13") (pin "14") (pinfunction "T1OUT_14") (pintype "output"))
    )
  )
)
